# e1-tracer.net
KiCad netlist of a schematic drawn in EAGLE
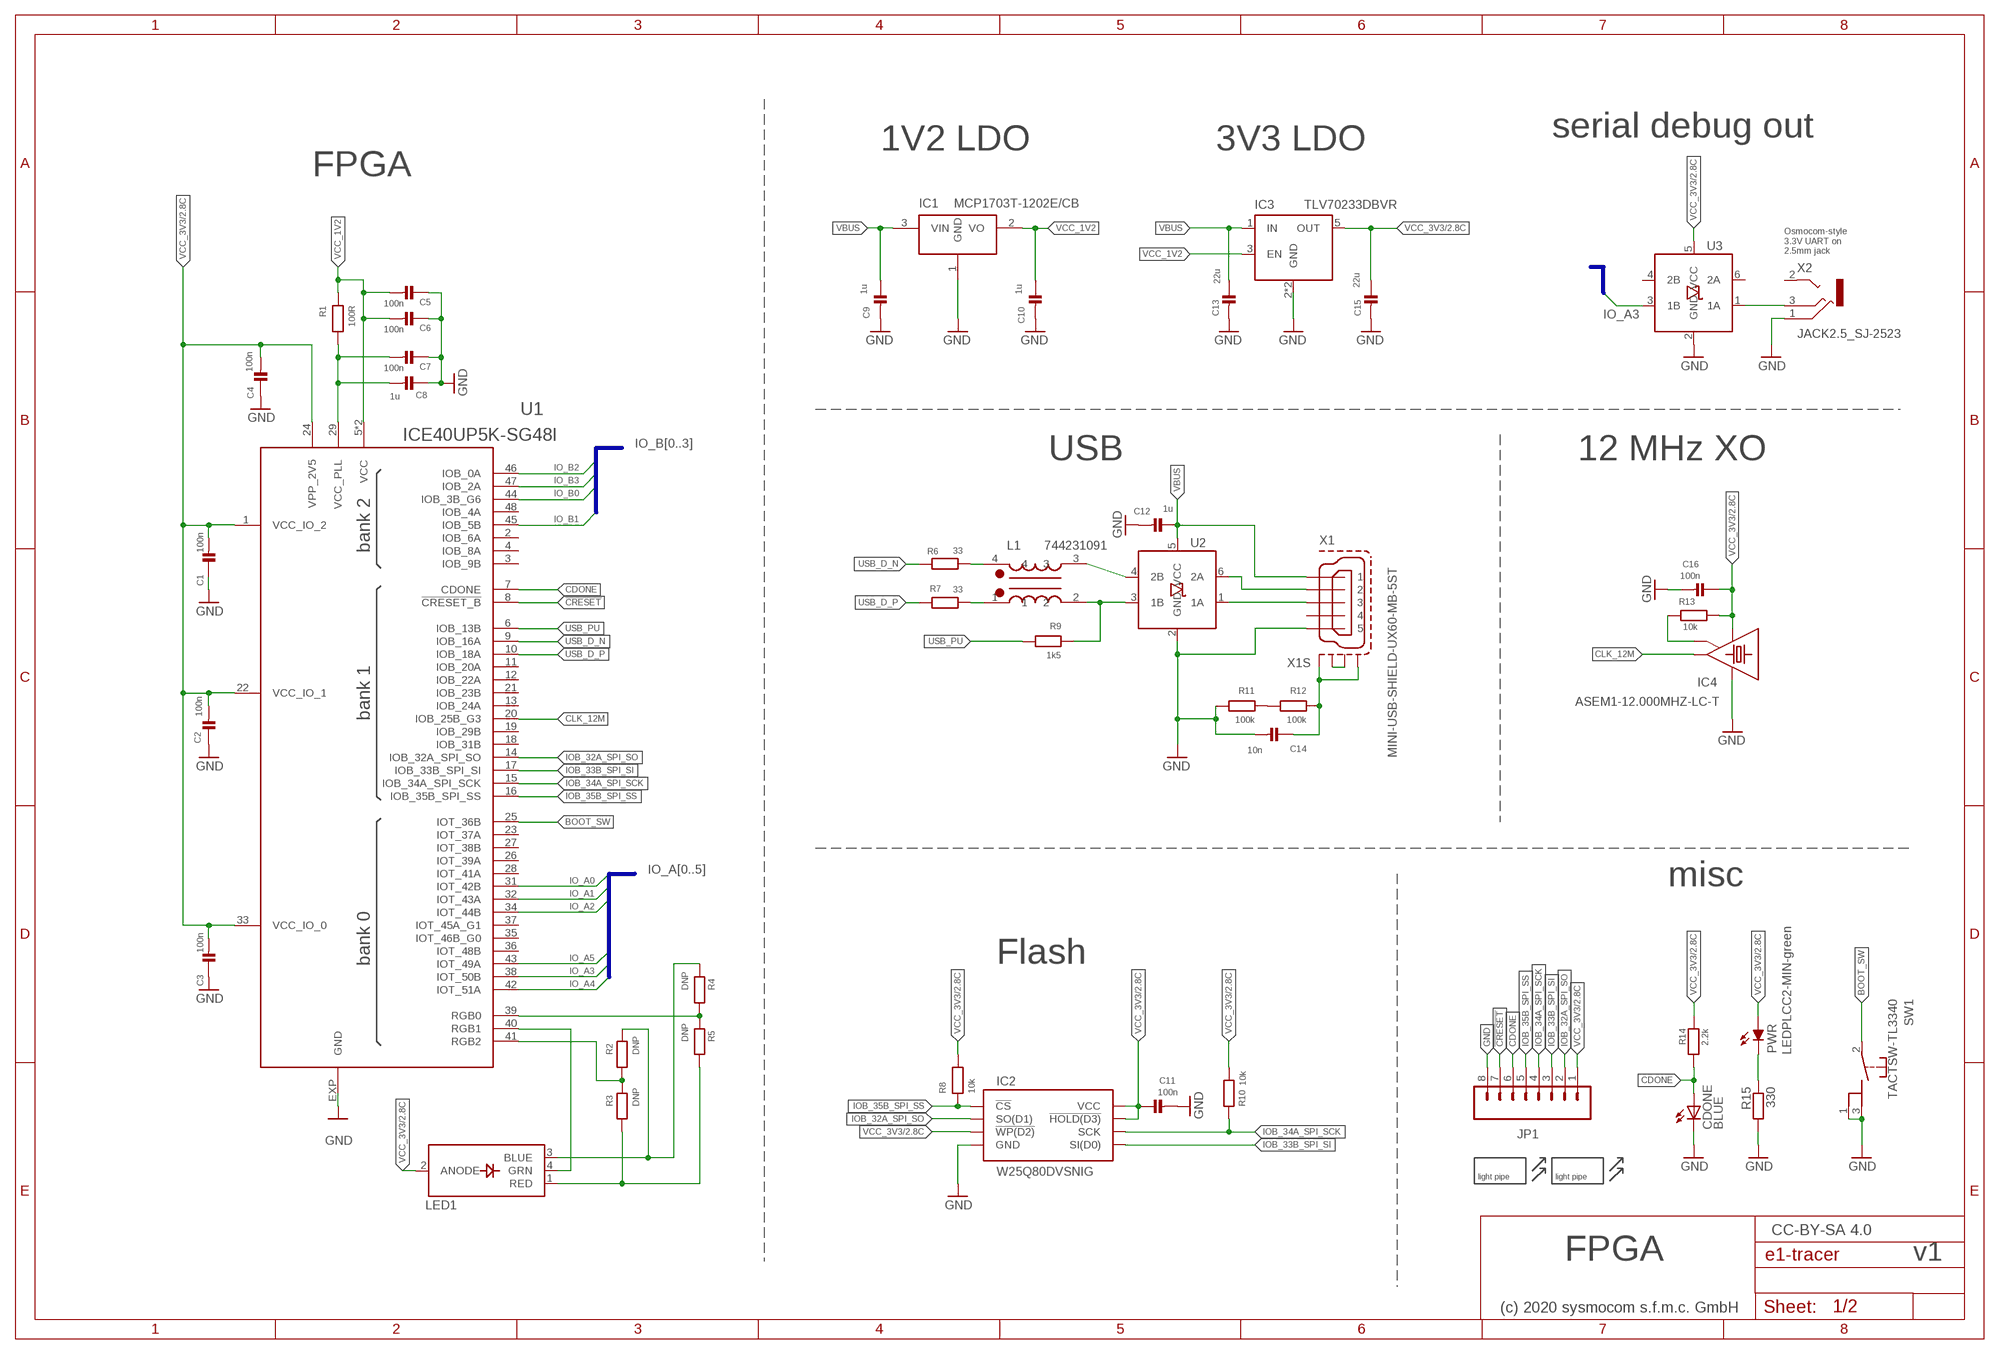
[diagram p0: schematic, sheet 1]
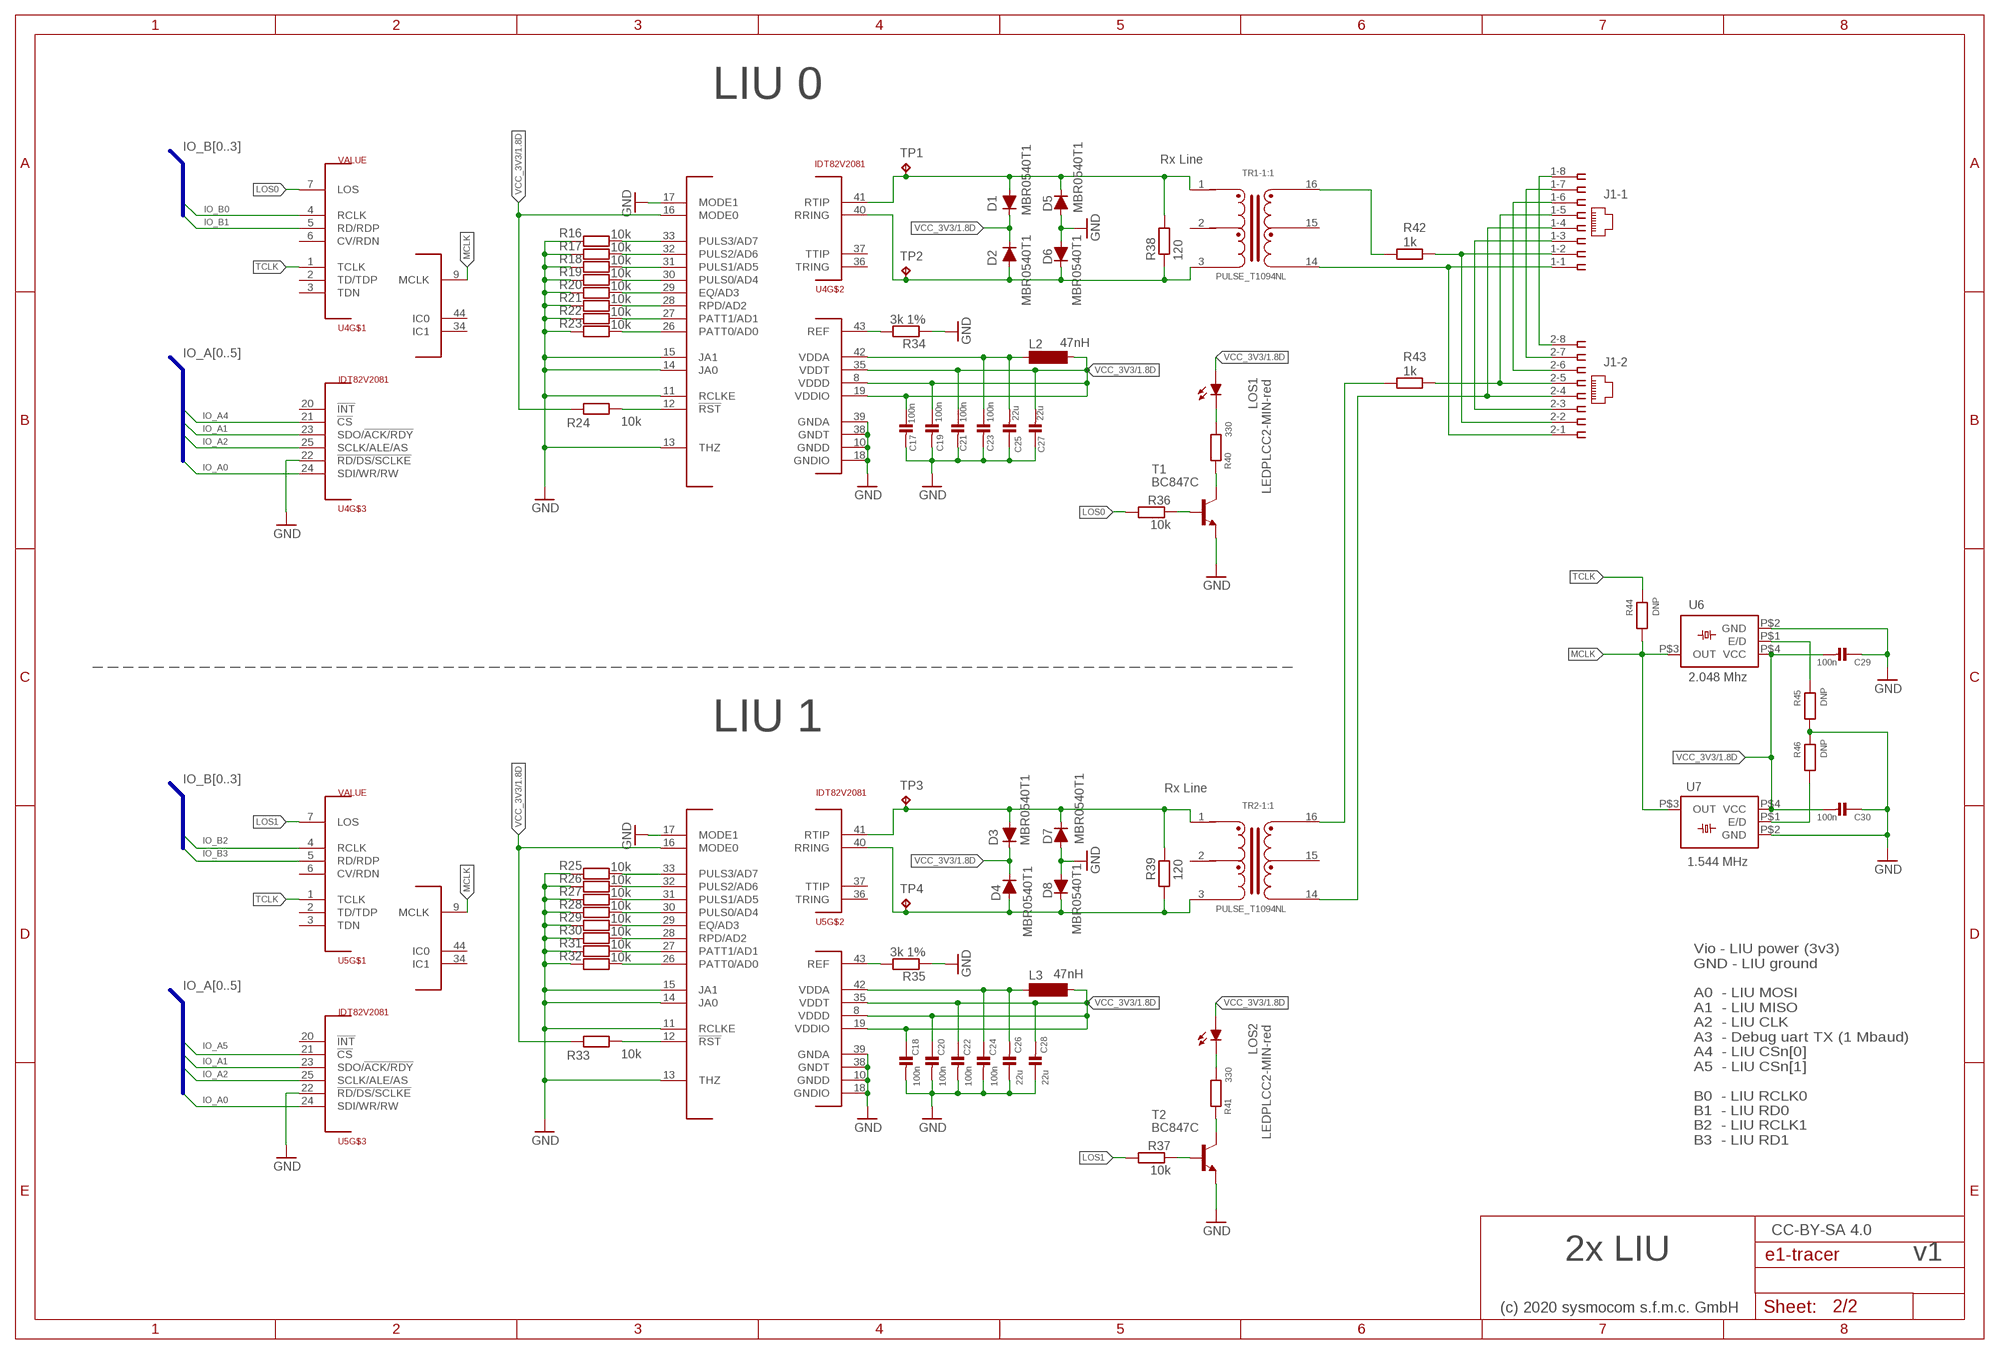
[diagram p1: schematic, sheet 2]

(export (version "E")
  (design (tool "Eeschema 10.0.6"))
  (components
    (comp (ref "C1")
      (value "100n")
      (footprint "eagle-import:_0603")
      (description "CAP CER 0.1UF 16V 10% X7R 0603")
      (fields
        (field (name "MANUFACTURER") "Samsung Electro-Mechanics America, Inc")
        (field (name "MANUFACTURERPARTNUMBER") "CL10B104KO8NNNC")
      )
      (libsource (lib "eagle-import") (part "CAP_CERAMIC_0603"))
    )
    (comp (ref "C2")
      (value "100n")
      (footprint "eagle-import:_0603")
      (description "CAP CER 0.1UF 16V 10% X7R 0603")
      (fields
        (field (name "MANUFACTURER") "Samsung Electro-Mechanics America, Inc")
        (field (name "MANUFACTURERPARTNUMBER") "CL10B104KO8NNNC")
      )
      (libsource (lib "eagle-import") (part "CAP_CERAMIC_0603"))
    )
    (comp (ref "C3")
      (value "100n")
      (footprint "eagle-import:_0603")
      (description "CAP CER 0.1UF 16V 10% X7R 0603")
      (fields
        (field (name "MANUFACTURER") "Samsung Electro-Mechanics America, Inc")
        (field (name "MANUFACTURERPARTNUMBER") "CL10B104KO8NNNC")
      )
      (libsource (lib "eagle-import") (part "CAP_CERAMIC_0603"))
    )
    (comp (ref "C4")
      (value "100n")
      (footprint "eagle-import:_0603")
      (description "CAP CER 0.1UF 16V 10% X7R 0603")
      (fields
        (field (name "MANUFACTURER") "Samsung Electro-Mechanics America, Inc")
        (field (name "MANUFACTURERPARTNUMBER") "CL10B104KO8NNNC")
      )
      (libsource (lib "eagle-import") (part "CAP_CERAMIC_0603"))
    )
    (comp (ref "C5")
      (value "100n")
      (footprint "eagle-import:_0603")
      (description "CAP CER 0.1UF 16V 10% X7R 0603")
      (fields
        (field (name "MANUFACTURER") "Samsung Electro-Mechanics America, Inc")
        (field (name "MANUFACTURERPARTNUMBER") "CL10B104KO8NNNC")
      )
      (libsource (lib "eagle-import") (part "CAP_CERAMIC_0603"))
    )
    (comp (ref "C6")
      (value "100n")
      (footprint "eagle-import:_0603")
      (description "CAP CER 0.1UF 16V 10% X7R 0603")
      (fields
        (field (name "MANUFACTURER") "Samsung Electro-Mechanics America, Inc")
        (field (name "MANUFACTURERPARTNUMBER") "CL10B104KO8NNNC")
      )
      (libsource (lib "eagle-import") (part "CAP_CERAMIC_0603"))
    )
    (comp (ref "C7")
      (value "100n")
      (footprint "eagle-import:_0603")
      (description "CAP CER 0.1UF 16V 10% X7R 0603")
      (fields
        (field (name "MANUFACTURER") "Samsung Electro-Mechanics America, Inc")
        (field (name "MANUFACTURERPARTNUMBER") "CL10B104KO8NNNC")
      )
      (libsource (lib "eagle-import") (part "CAP_CERAMIC_0603"))
    )
    (comp (ref "C8")
      (value "1u")
      (footprint "eagle-import:_0603")
      (description "CAP CER 1UF 10V X5R 0603")
      (fields
        (field (name "MANUFACTURER") "Samsung Electro-Mechanics")
        (field (name "MANUFACTURERPARTNUMBER") "CL10A105KP8NNNC")
      )
      (libsource (lib "eagle-import") (part "CAP_CERAMIC_0603"))
    )
    (comp (ref "C9")
      (value "1u")
      (footprint "eagle-import:_0603")
      (description "CAP CER 1UF 10V X5R 0603")
      (fields
        (field (name "MANUFACTURER") "Samsung Electro-Mechanics")
        (field (name "MANUFACTURERPARTNUMBER") "CL10A105KP8NNNC")
      )
      (libsource (lib "eagle-import") (part "CAP_CERAMIC_0603"))
    )
    (comp (ref "C10")
      (value "1u")
      (footprint "eagle-import:_0603")
      (description "CAP CER 1UF 10V X5R 0603")
      (fields
        (field (name "MANUFACTURER") "Samsung Electro-Mechanics")
        (field (name "MANUFACTURERPARTNUMBER") "CL10A105KP8NNNC")
      )
      (libsource (lib "eagle-import") (part "CAP_CERAMIC_0603"))
    )
    (comp (ref "C11")
      (value "100n")
      (footprint "eagle-import:_0603")
      (description "CAP CER 0.1UF 16V 10% X7R 0603")
      (fields
        (field (name "MANUFACTURER") "Samsung Electro-Mechanics America, Inc")
        (field (name "MANUFACTURERPARTNUMBER") "CL10B104KO8NNNC")
      )
      (libsource (lib "eagle-import") (part "CAP_CERAMIC_0603"))
    )
    (comp (ref "C12")
      (value "1u")
      (footprint "eagle-import:_0603")
      (description "CAP CER 1UF 10V X5R 0603")
      (fields
        (field (name "MANUFACTURER") "Samsung Electro-Mechanics")
        (field (name "MANUFACTURERPARTNUMBER") "CL10A105KP8NNNC")
      )
      (libsource (lib "eagle-import") (part "CAP_CERAMIC_0603"))
    )
    (comp (ref "C13")
      (value "22u")
      (footprint "eagle-import:1206")
      (description "CAP CER 22UF 10V 10% X5R 1206")
      (fields
        (field (name "MANUFACTURER") "Samsung Electro-Mechanics America, Inc")
        (field (name "MANUFACTURERPARTNUMBER") "CL31A226KPHNNNE")
      )
      (libsource (lib "eagle-import") (part "CAP_CERAMIC1206"))
    )
    (comp (ref "C14")
      (value "10n")
      (footprint "eagle-import:_0402")
      (description "CAP CER 10000PF 25V X7R 0402")
      (fields
        (field (name "MANUFACTURER") "Samsung Electro-Mechanics")
        (field (name "MANUFACTURERPARTNUMBER") "CL05B103KA5NNNC")
      )
      (libsource (lib "eagle-import") (part "CAP_CERAMIC_0402"))
    )
    (comp (ref "C15")
      (value "22u")
      (footprint "eagle-import:1206")
      (description "CAP CER 22UF 10V 10% X5R 1206")
      (fields
        (field (name "MANUFACTURER") "Samsung Electro-Mechanics America, Inc")
        (field (name "MANUFACTURERPARTNUMBER") "CL31A226KPHNNNE")
      )
      (libsource (lib "eagle-import") (part "CAP_CERAMIC1206"))
    )
    (comp (ref "C16")
      (value "100n")
      (footprint "eagle-import:_0603")
      (description "CAP CER 0.1UF 16V 10% X7R 0603")
      (fields
        (field (name "MANUFACTURER") "Samsung Electro-Mechanics America, Inc")
        (field (name "MANUFACTURERPARTNUMBER") "CL10B104KO8NNNC")
      )
      (libsource (lib "eagle-import") (part "CAP_CERAMIC_0603"))
    )
    (comp (ref "CDONE")
      (value "BLUE")
      (footprint "eagle-import:CHIPLED_0603")
      (description "LED BLUE CLEAR CHIP SMD")
      (fields
        (field (name "MANUFACTURER") "Lite-On Inc.")
        (field (name "MANUFACTURERPARTNUMBER") "LTST-C193TBKT-5A")
      )
      (libsource (lib "eagle-import") (part "LEDCHIPLED_0603"))
    )
    (comp (ref "IC1")
      (value "MCP1703T-1202E/CB")
      (footprint "eagle-import:SOT23-3")
      (description "IC REG LIN 1.2V 200MA SOT23A-3")
      (fields (field (name "MANUFACTURER") "Microchip Technology"))
      (libsource (lib "eagle-import") (part "MCP1700"))
    )
    (comp (ref "IC2")
      (value "W25Q80DVSNIG")
      (footprint "eagle-import:SO08COMBINED")
      (description "IC FLASH 8M SPI 104MHZ 8SOIC")
      (fields (field (name "MANUFACTURER") "Winbond Electronics"))
      (libsource (lib "eagle-import") (part "AT25SF-COMB"))
    )
    (comp (ref "IC3")
      (value "TLV70233DBVR")
      (footprint "eagle-import:SOT23-DBV")
      (description "IC REG LINEAR 3.3V 300MA SOT23-5")
      (fields (field (name "MANUFACTURER") "Texas Instruments") (field (name "OC_DIGIKEY") "296-32415-1-ND"))
      (libsource (lib "eagle-import") (part "TLV700-SOT33"))
    )
    (comp (ref "IC4")
      (value "ASEM1-12.000MHZ-LC-T")
      (footprint "eagle-import:TSX-3225")
      (description "MEMS OSC XO 12.0000MHZ CMOS SMD")
      (fields (field (name "MANUFACTURER") "Abracon LLC"))
      (libsource (lib "eagle-import") (part "ASTMLP-E-OSC"))
    )
    (comp (ref "JP1")
      (value "M08LOCK")
      (footprint "eagle-import:1X08_LOCK")
      (description "NO DESCRIPTION")
      (fields
        (field (name "MANUFACTURER") "UNKNOWN MANUFACTURER")
        (field (name "MANUFACTURERPARTNUMBER") "UNKNOWN MANUFACTURER PART NUMBER")
      )
      (libsource (lib "eagle-import") (part "M08LOCK"))
    )
    (comp (ref "L1")
      (value "744231091")
      (footprint "eagle-import:WE-CNSW_0805")
      (description "CMC 370MA 2LN 90 OHM SMD")
      (fields (field (name "MANUFACTURER") "Wurth Electronics Inc."))
      (libsource (lib "eagle-import") (part "WE-CNSW_0805"))
    )
    (comp (ref "LED1")
      (value "LED_RGB_PLCC4")
      (footprint "eagle-import:RGBLED_PLCC4")
      (description "LED RGB DIFFUSED 4PLCC SMD")
      (fields
        (field (name "MANUFACTURER") "TT Electronics/Optek Technology")
        (field (name "MANUFACTURERPARTNUMBER") "OVSARGB4R8")
      )
      (libsource (lib "eagle-import") (part "LED_RGB_PLCC4"))
    )
    (comp (ref "M1")
      (value "MENTOR_12701001")
      (footprint "eagle-import:1270.1001")
      (description "NO DESCRIPTION")
      (fields (field (name "MANUFACTURER") "Mentor") (field (name "MANUFACTURERPARTNUMBER") "1270.1001"))
      (libsource (lib "eagle-import") (part "MENTOR_12701001"))
    )
    (comp (ref "M2")
      (value "MENTOR_12701001")
      (footprint "eagle-import:1270.1001")
      (description "NO DESCRIPTION")
      (fields (field (name "MANUFACTURER") "Mentor") (field (name "MANUFACTURERPARTNUMBER") "1270.1001"))
      (libsource (lib "eagle-import") (part "MENTOR_12701001"))
    )
    (comp (ref "PWR")
      (value "LEDPLCC2-MIN-green")
      (footprint "eagle-import:PLCC2-MIN")
      (description "LED GREEN CLEAR 2PLCC SMD")
      (fields
        (field (name "MANUFACTURER") "Rohm Semiconductor")
        (field (name "MANUFACTURERPARTNUMBER") "SML-Z14PTT86A")
      )
      (libsource (lib "eagle-import") (part "LEDPLCC2-MIN"))
    )
    (comp (ref "R1")
      (value "100R")
      (footprint "eagle-import:_0603")
      (description "RES 100 OHM 5%% 1/10W 0603")
      (fields
        (field (name "MANUFACTURER") "Stackpole Electronics Inc")
        (field (name "MANUFACTURERPARTNUMBER") "RMCF0603JT100R")
      )
      (libsource (lib "eagle-import") (part "RESISTOR_0603"))
    )
    (comp (ref "R2")
      (value "DNP")
      (footprint "eagle-import:_0603")
      (description "RES SMD 0 OHM JUMPER 1/10W 0603")
      (fields
        (field (name "MANUFACTURER") "Panasonic Electronic Components")
        (field (name "MANUFACTURERPARTNUMBER") "ERJ-3GEY0R00V")
      )
      (libsource (lib "eagle-import") (part "RESISTOR_0603"))
    )
    (comp (ref "R3")
      (value "DNP")
      (footprint "eagle-import:_0603")
      (description "RES SMD 0 OHM JUMPER 1/10W 0603")
      (fields
        (field (name "MANUFACTURER") "Panasonic Electronic Components")
        (field (name "MANUFACTURERPARTNUMBER") "ERJ-3GEY0R00V")
      )
      (libsource (lib "eagle-import") (part "RESISTOR_0603"))
    )
    (comp (ref "R4")
      (value "DNP")
      (footprint "eagle-import:_0603")
      (description "RES SMD 0 OHM JUMPER 1/10W 0603")
      (fields
        (field (name "MANUFACTURER") "Panasonic Electronic Components")
        (field (name "MANUFACTURERPARTNUMBER") "ERJ-3GEY0R00V")
      )
      (libsource (lib "eagle-import") (part "RESISTOR_0603"))
    )
    (comp (ref "R5")
      (value "DNP")
      (footprint "eagle-import:_0603")
      (description "RES SMD 0 OHM JUMPER 1/10W 0603")
      (fields
        (field (name "MANUFACTURER") "Panasonic Electronic Components")
        (field (name "MANUFACTURERPARTNUMBER") "ERJ-3GEY0R00V")
      )
      (libsource (lib "eagle-import") (part "RESISTOR_0603"))
    )
    (comp (ref "R6")
      (value "33")
      (footprint "eagle-import:_0402")
      (description "RES 33 OHM 5%% 1/10W 0603")
      (fields
        (field (name "MANUFACTURER") "Stackpole Electronics Inc")
        (field (name "MANUFACTURERPARTNUMBER") "RMCF0603JT33R0")
      )
      (libsource (lib "eagle-import") (part "RESISTOR_0402"))
    )
    (comp (ref "R7")
      (value "33")
      (footprint "eagle-import:_0402")
      (description "RES 33 OHM 5%% 1/10W 0603")
      (fields
        (field (name "MANUFACTURER") "Stackpole Electronics Inc")
        (field (name "MANUFACTURERPARTNUMBER") "RMCF0603JT33R0")
      )
      (libsource (lib "eagle-import") (part "RESISTOR_0402"))
    )
    (comp (ref "R8")
      (value "10k")
      (footprint "eagle-import:_0603")
      (description "RES 10K OHM 5%% 1/10W 0603")
      (fields
        (field (name "MANUFACTURER") "Stackpole Electronics Inc")
        (field (name "MANUFACTURERPARTNUMBER") "RMCF0603JT10K0")
      )
      (libsource (lib "eagle-import") (part "RESISTOR_0603"))
    )
    (comp (ref "R9")
      (value "1k5")
      (footprint "eagle-import:_0603")
      (description "RES 1.5K OHM 5%% 1/10W 0603")
      (fields
        (field (name "MANUFACTURER") "Stackpole Electronics Inc")
        (field (name "MANUFACTURERPARTNUMBER") "RMCF0603JT1K50")
      )
      (libsource (lib "eagle-import") (part "RESISTOR_0603"))
    )
    (comp (ref "R10")
      (value "10k")
      (footprint "eagle-import:_0603")
      (description "RES 10K OHM 5%% 1/10W 0603")
      (fields
        (field (name "MANUFACTURER") "Stackpole Electronics Inc")
        (field (name "MANUFACTURERPARTNUMBER") "RMCF0603JT10K0")
      )
      (libsource (lib "eagle-import") (part "RESISTOR_0603"))
    )
    (comp (ref "R11")
      (value "100k")
      (footprint "eagle-import:_0603")
      (description "RES SMD 100K OHM 5%% 1/10W 0603")
      (fields
        (field (name "MANUFACTURER") "Yageo")
        (field (name "MANUFACTURERPARTNUMBER") "RC0603JR-07100KL")
      )
      (libsource (lib "eagle-import") (part "RESISTOR_0603"))
    )
    (comp (ref "R12")
      (value "100k")
      (footprint "eagle-import:_0603")
      (description "RES SMD 100K OHM 5%% 1/10W 0603")
      (fields
        (field (name "MANUFACTURER") "Yageo")
        (field (name "MANUFACTURERPARTNUMBER") "RC0603JR-07100KL")
      )
      (libsource (lib "eagle-import") (part "RESISTOR_0603"))
    )
    (comp (ref "R13")
      (value "10k")
      (footprint "eagle-import:_0603")
      (description "RES 10K OHM 5%% 1/10W 0603")
      (fields
        (field (name "MANUFACTURER") "Stackpole Electronics Inc")
        (field (name "MANUFACTURERPARTNUMBER") "RMCF0603JT10K0")
      )
      (libsource (lib "eagle-import") (part "RESISTOR_0603"))
    )
    (comp (ref "R14")
      (value "2.2k")
      (footprint "eagle-import:_0603")
      (description "RES 2.2K OHM 5%% 1/10W 0603")
      (fields
        (field (name "MANUFACTURER") "Stackpole Electronics Inc")
        (field (name "MANUFACTURERPARTNUMBER") "RMCF0603JT2K20")
      )
      (libsource (lib "eagle-import") (part "RESISTOR_0603"))
    )
    (comp (ref "R15")
      (value "330")
      (footprint "eagle-import:_0603")
      (description "RES SMD 330 OHM 1%% 1/10W 0603")
      (fields
        (field (name "MANUFACTURER") "Yageo")
        (field (name "MANUFACTURERPARTNUMBER") "RC0603FR-07330RL")
      )
      (libsource (lib "eagle-import") (part "RESISTOR_0603"))
    )
    (comp (ref "SW1")
      (value "TACTSW-TL3340")
      (footprint "eagle-import:TL3340-ORIG")
      (description "SWITCH TACTILE SPST-NO 0.05A 12V")
      (fields
        (field (name "MANUFACTURER") "E-Switch")
        (field (name "MANUFACTURERPARTNUMBER") "TL3340AF160QG")
      )
      (libsource (lib "eagle-import") (part "TL3340"))
    )
    (comp (ref "U1")
      (value "ICE40UP5K-SG48I")
      (footprint "eagle-import:QFN48")
      (description "IC FPGA 39 I/O 48QFN")
      (fields (field (name "MANUFACTURER") "Lattice Semiconductor Corporation"))
      (libsource (lib "eagle-import") (part "ICE40UP5K-SG48I"))
    )
    (comp (ref "U2")
      (value "IP4234CZ6")
      (footprint "eagle-import:TSOP-6")
      (description "TVS DIODE 5.5V 6TSOP")
      (fields
        (field (name "MANUFACTURER") "Nexperia USA Inc.")
        (field (name "MANUFACTURERPARTNUMBER") "IP4234CZ6,125")
      )
      (libsource (lib "eagle-import") (part "IP4234CZ6"))
    )
    (comp (ref "U3")
      (value "IP4234CZ6")
      (footprint "eagle-import:TSOP-6")
      (description "TVS DIODE 5.5V 6TSOP")
      (fields
        (field (name "MANUFACTURER") "Nexperia USA Inc.")
        (field (name "MANUFACTURERPARTNUMBER") "IP4234CZ6,125")
      )
      (libsource (lib "eagle-import") (part "IP4234CZ6"))
    )
    (comp (ref "X1")
      (value "MINI-USB-SHIELD-UX60-MB-5ST")
      (footprint "eagle-import:UX60-MB-5ST")
      (description "CONN RCPT USB2.0 MINI B SMD R/A")
      (fields
        (field (name "MANUFACTURER") "Hirose Electric Co Ltd")
        (field (name "MANUFACTURERPARTNUMBER") "UX60A-MB-5ST")
        (field (name "CLASS") "CONNECTOR")
        (field (name "LINK") "https://www.digikey.de/product-detail/de/hirose-electric-co-ltd/UX60A-MB-5ST/H2961CT-ND/597540")
        (field (name "POPULATED") "TRUE")
        (field (name "ROHSCERTIFICATE") "Bleifrei / RoHS-konform")
        (field (name "SOURCE") "DIGIKEY")
        (field (name "SOURCEPARTNUMBER") "H2961CT-ND")
      )
      (libsource (lib "eagle-import") (part "MINI-USB-SHIELD-UX60-MB-5ST"))
    )
    (comp (ref "X2")
      (value "JACK2.5_SJ-2523")
      (footprint "eagle-import:JACK2.5_SJ-2523")
      (description "CONN JACK STEREO 2.5MM SMD R/A")
      (fields
        (field (name "MANUFACTURER") "CUI Inc.")
        (field (name "MANUFACTURERPARTNUMBER") "SJ-2523-SMT-TR")
      )
      (libsource (lib "eagle-import") (part "JACK2.5_SJ-2523"))
    )
    (comp (ref "C17")
      (value "100n")
      (footprint "eagle-import:_0603")
      (description "CAP CER 0.1UF 16V 10% X7R 0603")
      (fields
        (field (name "MANUFACTURER") "Samsung Electro-Mechanics America, Inc")
        (field (name "MANUFACTURERPARTNUMBER") "CL10B104KO8NNNC")
      )
      (libsource (lib "eagle-import") (part "CAP_CERAMIC_0603"))
    )
    (comp (ref "C18")
      (value "100n")
      (footprint "eagle-import:_0603")
      (description "CAP CER 0.1UF 16V 10% X7R 0603")
      (fields
        (field (name "MANUFACTURER") "Samsung Electro-Mechanics America, Inc")
        (field (name "MANUFACTURERPARTNUMBER") "CL10B104KO8NNNC")
      )
      (libsource (lib "eagle-import") (part "CAP_CERAMIC_0603"))
    )
    (comp (ref "C19")
      (value "100n")
      (footprint "eagle-import:_0603")
      (description "CAP CER 0.1UF 16V 10% X7R 0603")
      (fields
        (field (name "MANUFACTURER") "Samsung Electro-Mechanics America, Inc")
        (field (name "MANUFACTURERPARTNUMBER") "CL10B104KO8NNNC")
      )
      (libsource (lib "eagle-import") (part "CAP_CERAMIC_0603"))
    )
    (comp (ref "C20")
      (value "100n")
      (footprint "eagle-import:_0603")
      (description "CAP CER 0.1UF 16V 10% X7R 0603")
      (fields
        (field (name "MANUFACTURER") "Samsung Electro-Mechanics America, Inc")
        (field (name "MANUFACTURERPARTNUMBER") "CL10B104KO8NNNC")
      )
      (libsource (lib "eagle-import") (part "CAP_CERAMIC_0603"))
    )
    (comp (ref "C21")
      (value "100n")
      (footprint "eagle-import:_0603")
      (description "CAP CER 0.1UF 16V 10% X7R 0603")
      (fields
        (field (name "MANUFACTURER") "Samsung Electro-Mechanics America, Inc")
        (field (name "MANUFACTURERPARTNUMBER") "CL10B104KO8NNNC")
      )
      (libsource (lib "eagle-import") (part "CAP_CERAMIC_0603"))
    )
    (comp (ref "C22")
      (value "100n")
      (footprint "eagle-import:_0603")
      (description "CAP CER 0.1UF 16V 10% X7R 0603")
      (fields
        (field (name "MANUFACTURER") "Samsung Electro-Mechanics America, Inc")
        (field (name "MANUFACTURERPARTNUMBER") "CL10B104KO8NNNC")
      )
      (libsource (lib "eagle-import") (part "CAP_CERAMIC_0603"))
    )
    (comp (ref "C23")
      (value "100n")
      (footprint "eagle-import:_0603")
      (description "CAP CER 0.1UF 16V 10% X7R 0603")
      (fields
        (field (name "MANUFACTURER") "Samsung Electro-Mechanics America, Inc")
        (field (name "MANUFACTURERPARTNUMBER") "CL10B104KO8NNNC")
      )
      (libsource (lib "eagle-import") (part "CAP_CERAMIC_0603"))
    )
    (comp (ref "C24")
      (value "100n")
      (footprint "eagle-import:_0603")
      (description "CAP CER 0.1UF 16V 10% X7R 0603")
      (fields
        (field (name "MANUFACTURER") "Samsung Electro-Mechanics America, Inc")
        (field (name "MANUFACTURERPARTNUMBER") "CL10B104KO8NNNC")
      )
      (libsource (lib "eagle-import") (part "CAP_CERAMIC_0603"))
    )
    (comp (ref "C25")
      (value "22u")
      (footprint "eagle-import:_0805")
      (description "CAP CER 22UF 6.3V X5R 0805")
      (fields
        (field (name "MANUFACTURER") "KEMET")
        (field (name "MANUFACTURERPARTNUMBER") "C0805C226M9PACTU")
      )
      (libsource (lib "eagle-import") (part "CAP_CERAMIC_0805"))
    )
    (comp (ref "C26")
      (value "22u")
      (footprint "eagle-import:_0805")
      (description "CAP CER 22UF 6.3V X5R 0805")
      (fields
        (field (name "MANUFACTURER") "KEMET")
        (field (name "MANUFACTURERPARTNUMBER") "C0805C226M9PACTU")
      )
      (libsource (lib "eagle-import") (part "CAP_CERAMIC_0805"))
    )
    (comp (ref "C27")
      (value "22u")
      (footprint "eagle-import:_0805")
      (description "CAP CER 22UF 6.3V X5R 0805")
      (fields
        (field (name "MANUFACTURER") "KEMET")
        (field (name "MANUFACTURERPARTNUMBER") "C0805C226M9PACTU")
      )
      (libsource (lib "eagle-import") (part "CAP_CERAMIC_0805"))
    )
    (comp (ref "C28")
      (value "22u")
      (footprint "eagle-import:_0805")
      (description "CAP CER 22UF 6.3V X5R 0805")
      (fields
        (field (name "MANUFACTURER") "KEMET")
        (field (name "MANUFACTURERPARTNUMBER") "C0805C226M9PACTU")
      )
      (libsource (lib "eagle-import") (part "CAP_CERAMIC_0805"))
    )
    (comp (ref "C29")
      (value "100n")
      (footprint "eagle-import:_0603")
      (description "CAP CER 0.1UF 16V 10% X7R 0603")
      (fields
        (field (name "MANUFACTURER") "Samsung Electro-Mechanics America, Inc")
        (field (name "MANUFACTURERPARTNUMBER") "CL10B104KO8NNNC")
      )
      (libsource (lib "eagle-import") (part "CAP_CERAMIC_0603"))
    )
    (comp (ref "C30")
      (value "100n")
      (footprint "eagle-import:_0603")
      (description "CAP CER 0.1UF 16V 10% X7R 0603")
      (fields
        (field (name "MANUFACTURER") "Samsung Electro-Mechanics America, Inc")
        (field (name "MANUFACTURERPARTNUMBER") "CL10B104KO8NNNC")
      )
      (libsource (lib "eagle-import") (part "CAP_CERAMIC_0603"))
    )
    (comp (ref "D1")
      (value "MBR0540T1")
      (footprint "eagle-import:SOD123")
      (description "DIODE SCHOTTKY 40V 500MA SOD123")
      (fields
        (field (name "MANUFACTURER") "ON Semiconductor")
        (field (name "MANUFACTURERPARTNUMBER") "MBR0540T1G")
      )
      (libsource (lib "eagle-import") (part "D-FILL-SOD123"))
    )
    (comp (ref "D2")
      (value "MBR0540T1")
      (footprint "eagle-import:SOD123")
      (description "DIODE SCHOTTKY 40V 500MA SOD123")
      (fields
        (field (name "MANUFACTURER") "ON Semiconductor")
        (field (name "MANUFACTURERPARTNUMBER") "MBR0540T1G")
      )
      (libsource (lib "eagle-import") (part "D-FILL-SOD123"))
    )
    (comp (ref "D3")
      (value "MBR0540T1")
      (footprint "eagle-import:SOD123")
      (description "DIODE SCHOTTKY 40V 500MA SOD123")
      (fields
        (field (name "MANUFACTURER") "ON Semiconductor")
        (field (name "MANUFACTURERPARTNUMBER") "MBR0540T1G")
      )
      (libsource (lib "eagle-import") (part "D-FILL-SOD123"))
    )
    (comp (ref "D4")
      (value "MBR0540T1")
      (footprint "eagle-import:SOD123")
      (description "DIODE SCHOTTKY 40V 500MA SOD123")
      (fields
        (field (name "MANUFACTURER") "ON Semiconductor")
        (field (name "MANUFACTURERPARTNUMBER") "MBR0540T1G")
      )
      (libsource (lib "eagle-import") (part "D-FILL-SOD123"))
    )
    (comp (ref "D5")
      (value "MBR0540T1")
      (footprint "eagle-import:SOD123")
      (description "DIODE SCHOTTKY 40V 500MA SOD123")
      (fields
        (field (name "MANUFACTURER") "ON Semiconductor")
        (field (name "MANUFACTURERPARTNUMBER") "MBR0540T1G")
      )
      (libsource (lib "eagle-import") (part "D-FILL-SOD123"))
    )
    (comp (ref "D6")
      (value "MBR0540T1")
      (footprint "eagle-import:SOD123")
      (description "DIODE SCHOTTKY 40V 500MA SOD123")
      (fields
        (field (name "MANUFACTURER") "ON Semiconductor")
        (field (name "MANUFACTURERPARTNUMBER") "MBR0540T1G")
      )
      (libsource (lib "eagle-import") (part "D-FILL-SOD123"))
    )
    (comp (ref "D7")
      (value "MBR0540T1")
      (footprint "eagle-import:SOD123")
      (description "DIODE SCHOTTKY 40V 500MA SOD123")
      (fields
        (field (name "MANUFACTURER") "ON Semiconductor")
        (field (name "MANUFACTURERPARTNUMBER") "MBR0540T1G")
      )
      (libsource (lib "eagle-import") (part "D-FILL-SOD123"))
    )
    (comp (ref "D8")
      (value "MBR0540T1")
      (footprint "eagle-import:SOD123")
      (description "DIODE SCHOTTKY 40V 500MA SOD123")
      (fields
        (field (name "MANUFACTURER") "ON Semiconductor")
        (field (name "MANUFACTURERPARTNUMBER") "MBR0540T1G")
      )
      (libsource (lib "eagle-import") (part "D-FILL-SOD123"))
    )
    (comp (ref "J1")
      (value "PASSTHROUGH")
      (footprint "eagle-import:557560-1")
      (description "CONN MOD JACK 8P8C R/A UNSHLD")
      (fields
        (field (name "MANUFACTURER") "TE Connectivity AMP Connectors")
        (field (name "MANUFACTURERPARTNUMBER") "5557560-1")
        (field (name "CLASS") "CONNECTOR\\JUMPER")
        (field (name "LINK") "https://www.digikey.de/product-detail/de/te-connectivity-amp-connectors/5557560-1/A31449-ND")
        (field (name "POPULATED") "TRUE")
        (field (name "ROHSCERTIFICATE") "UNKNOWN ROHS CERTIFICATE")
        (field (name "SOURCE") "DIGIKEY")
        (field (name "SOURCEPARTNUMBER") "A31449-ND")
      )
      (libsource (lib "eagle-import") (part "557560-1"))
    )
    (comp (ref "L2")
      (value "47nH")
      (footprint "eagle-import:SM-1206")
      (description "FIXED IND 47NH 300MA 700MOHM SMD")
      (fields
        (field (name "MANUFACTURER") "Bourns Inc.")
        (field (name "MANUFACTURERPARTNUMBER") "CE201210-47NJ")
      )
      (libsource (lib "eagle-import") (part "SM-1206"))
    )
    (comp (ref "L3")
      (value "47nH")
      (footprint "eagle-import:SM-1206")
      (description "FIXED IND 47NH 300MA 700MOHM SMD")
      (fields
        (field (name "MANUFACTURER") "Bourns Inc.")
        (field (name "MANUFACTURERPARTNUMBER") "CE201210-47NJ")
      )
      (libsource (lib "eagle-import") (part "SM-1206"))
    )
    (comp (ref "LOS1")
      (value "LEDPLCC2-MIN-red")
      (footprint "eagle-import:PLCC2-MIN")
      (description "LED RED CLEAR 2PLCC SMD")
      (fields
        (field (name "MANUFACTURER") "OSRAM Opto Semiconductors Inc.")
        (field (name "MANUFACTURERPARTNUMBER") "LS T676-R1S1-1-Z")
      )
      (libsource (lib "eagle-import") (part "LEDPLCC2-MIN"))
    )
    (comp (ref "LOS2")
      (value "LEDPLCC2-MIN-red")
      (footprint "eagle-import:PLCC2-MIN")
      (description "LED RED CLEAR 2PLCC SMD")
      (fields
        (field (name "MANUFACTURER") "OSRAM Opto Semiconductors Inc.")
        (field (name "MANUFACTURERPARTNUMBER") "LS T676-R1S1-1-Z")
      )
      (libsource (lib "eagle-import") (part "LEDPLCC2-MIN"))
    )
    (comp (ref "R16")
      (value "10k")
      (footprint "eagle-import:_0603")
      (description "RES 10K OHM 5%% 1/10W 0603")
      (fields
        (field (name "MANUFACTURER") "Stackpole Electronics Inc")
        (field (name "MANUFACTURERPARTNUMBER") "RMCF0603JT10K0")
      )
      (libsource (lib "eagle-import") (part "RESISTOR_0603"))
    )
    (comp (ref "R17")
      (value "10k")
      (footprint "eagle-import:_0603")
      (description "RES 10K OHM 5%% 1/10W 0603")
      (fields
        (field (name "MANUFACTURER") "Stackpole Electronics Inc")
        (field (name "MANUFACTURERPARTNUMBER") "RMCF0603JT10K0")
      )
      (libsource (lib "eagle-import") (part "RESISTOR_0603"))
    )
    (comp (ref "R18")
      (value "10k")
      (footprint "eagle-import:_0603")
      (description "RES 10K OHM 5%% 1/10W 0603")
      (fields
        (field (name "MANUFACTURER") "Stackpole Electronics Inc")
        (field (name "MANUFACTURERPARTNUMBER") "RMCF0603JT10K0")
      )
      (libsource (lib "eagle-import") (part "RESISTOR_0603"))
    )
    (comp (ref "R19")
      (value "10k")
      (footprint "eagle-import:_0603")
      (description "RES 10K OHM 5%% 1/10W 0603")
      (fields
        (field (name "MANUFACTURER") "Stackpole Electronics Inc")
        (field (name "MANUFACTURERPARTNUMBER") "RMCF0603JT10K0")
      )
      (libsource (lib "eagle-import") (part "RESISTOR_0603"))
    )
    (comp (ref "R20")
      (value "10k")
      (footprint "eagle-import:_0603")
      (description "RES 10K OHM 5%% 1/10W 0603")
      (fields
        (field (name "MANUFACTURER") "Stackpole Electronics Inc")
        (field (name "MANUFACTURERPARTNUMBER") "RMCF0603JT10K0")
      )
      (libsource (lib "eagle-import") (part "RESISTOR_0603"))
    )
    (comp (ref "R21")
      (value "10k")
      (footprint "eagle-import:_0603")
      (description "RES 10K OHM 5%% 1/10W 0603")
      (fields
        (field (name "MANUFACTURER") "Stackpole Electronics Inc")
        (field (name "MANUFACTURERPARTNUMBER") "RMCF0603JT10K0")
      )
      (libsource (lib "eagle-import") (part "RESISTOR_0603"))
    )
    (comp (ref "R22")
      (value "10k")
      (footprint "eagle-import:_0603")
      (description "RES 10K OHM 5%% 1/10W 0603")
      (fields
        (field (name "MANUFACTURER") "Stackpole Electronics Inc")
        (field (name "MANUFACTURERPARTNUMBER") "RMCF0603JT10K0")
      )
      (libsource (lib "eagle-import") (part "RESISTOR_0603"))
    )
    (comp (ref "R23")
      (value "10k")
      (footprint "eagle-import:_0603")
      (description "RES 10K OHM 5%% 1/10W 0603")
      (fields
        (field (name "MANUFACTURER") "Stackpole Electronics Inc")
        (field (name "MANUFACTURERPARTNUMBER") "RMCF0603JT10K0")
      )
      (libsource (lib "eagle-import") (part "RESISTOR_0603"))
    )
    (comp (ref "R24")
      (value "10k")
      (footprint "eagle-import:_0603")
      (description "RES 10K OHM 5%% 1/10W 0603")
      (fields
        (field (name "MANUFACTURER") "Stackpole Electronics Inc")
        (field (name "MANUFACTURERPARTNUMBER") "RMCF0603JT10K0")
      )
      (libsource (lib "eagle-import") (part "RESISTOR_0603"))
    )
    (comp (ref "R25")
      (value "10k")
      (footprint "eagle-import:_0603")
      (description "RES 10K OHM 5%% 1/10W 0603")
      (fields
        (field (name "MANUFACTURER") "Stackpole Electronics Inc")
        (field (name "MANUFACTURERPARTNUMBER") "RMCF0603JT10K0")
      )
      (libsource (lib "eagle-import") (part "RESISTOR_0603"))
    )
    (comp (ref "R26")
      (value "10k")
      (footprint "eagle-import:_0603")
      (description "RES 10K OHM 5%% 1/10W 0603")
      (fields
        (field (name "MANUFACTURER") "Stackpole Electronics Inc")
        (field (name "MANUFACTURERPARTNUMBER") "RMCF0603JT10K0")
      )
      (libsource (lib "eagle-import") (part "RESISTOR_0603"))
    )
    (comp (ref "R27")
      (value "10k")
      (footprint "eagle-import:_0603")
      (description "RES 10K OHM 5%% 1/10W 0603")
      (fields
        (field (name "MANUFACTURER") "Stackpole Electronics Inc")
        (field (name "MANUFACTURERPARTNUMBER") "RMCF0603JT10K0")
      )
      (libsource (lib "eagle-import") (part "RESISTOR_0603"))
    )
    (comp (ref "R28")
      (value "10k")
      (footprint "eagle-import:_0603")
      (description "RES 10K OHM 5%% 1/10W 0603")
      (fields
        (field (name "MANUFACTURER") "Stackpole Electronics Inc")
        (field (name "MANUFACTURERPARTNUMBER") "RMCF0603JT10K0")
      )
      (libsource (lib "eagle-import") (part "RESISTOR_0603"))
    )
    (comp (ref "R29")
      (value "10k")
      (footprint "eagle-import:_0603")
      (description "RES 10K OHM 5%% 1/10W 0603")
      (fields
        (field (name "MANUFACTURER") "Stackpole Electronics Inc")
        (field (name "MANUFACTURERPARTNUMBER") "RMCF0603JT10K0")
      )
      (libsource (lib "eagle-import") (part "RESISTOR_0603"))
    )
    (comp (ref "R30")
      (value "10k")
      (footprint "eagle-import:_0603")
      (description "RES 10K OHM 5%% 1/10W 0603")
      (fields
        (field (name "MANUFACTURER") "Stackpole Electronics Inc")
        (field (name "MANUFACTURERPARTNUMBER") "RMCF0603JT10K0")
      )
      (libsource (lib "eagle-import") (part "RESISTOR_0603"))
    )
    (comp (ref "R31")
      (value "10k")
      (footprint "eagle-import:_0603")
      (description "RES 10K OHM 5%% 1/10W 0603")
      (fields
        (field (name "MANUFACTURER") "Stackpole Electronics Inc")
        (field (name "MANUFACTURERPARTNUMBER") "RMCF0603JT10K0")
      )
      (libsource (lib "eagle-import") (part "RESISTOR_0603"))
    )
    (comp (ref "R32")
      (value "10k")
      (footprint "eagle-import:_0603")
      (description "RES 10K OHM 5%% 1/10W 0603")
      (fields
        (field (name "MANUFACTURER") "Stackpole Electronics Inc")
        (field (name "MANUFACTURERPARTNUMBER") "RMCF0603JT10K0")
      )
      (libsource (lib "eagle-import") (part "RESISTOR_0603"))
    )
    (comp (ref "R33")
      (value "10k")
      (footprint "eagle-import:_0603")
      (description "RES 10K OHM 5%% 1/10W 0603")
      (fields
        (field (name "MANUFACTURER") "Stackpole Electronics Inc")
        (field (name "MANUFACTURERPARTNUMBER") "RMCF0603JT10K0")
      )
      (libsource (lib "eagle-import") (part "RESISTOR_0603"))
    )
    (comp (ref "R34")
      (value "3k 1%")
      (footprint "eagle-import:_0603")
      (description "RES 3K OHM 1%% 1/10W 0603")
      (fields
        (field (name "MANUFACTURER") "Stackpole Electronics Inc")
        (field (name "MANUFACTURERPARTNUMBER") "RMCF0603FT3K00")
      )
      (libsource (lib "eagle-import") (part "RESISTOR_0603"))
    )
    (comp (ref "R35")
      (value "3k 1%")
      (footprint "eagle-import:_0603")
      (description "RES 3K OHM 1%% 1/10W 0603")
      (fields
        (field (name "MANUFACTURER") "Stackpole Electronics Inc")
        (field (name "MANUFACTURERPARTNUMBER") "RMCF0603FT3K00")
      )
      (libsource (lib "eagle-import") (part "RESISTOR_0603"))
    )
    (comp (ref "R36")
      (value "10k")
      (footprint "eagle-import:_0603")
      (description "RES 10K OHM 5%% 1/10W 0603")
      (fields
        (field (name "MANUFACTURER") "Stackpole Electronics Inc")
        (field (name "MANUFACTURERPARTNUMBER") "RMCF0603JT10K0")
      )
      (libsource (lib "eagle-import") (part "RESISTOR_0603"))
    )
    (comp (ref "R37")
      (value "10k")
      (footprint "eagle-import:_0603")
      (description "RES 10K OHM 5%% 1/10W 0603")
      (fields
        (field (name "MANUFACTURER") "Stackpole Electronics Inc")
        (field (name "MANUFACTURERPARTNUMBER") "RMCF0603JT10K0")
      )
      (libsource (lib "eagle-import") (part "RESISTOR_0603"))
    )
    (comp (ref "R38")
      (value "120")
      (footprint "eagle-import:_0603")
      (description "RES 120 OHM 5%% 1/10W 0603")
      (fields
        (field (name "MANUFACTURER") "Stackpole Electronics Inc")
        (field (name "MANUFACTURERPARTNUMBER") "RMCF0603JT120R")
      )
      (libsource (lib "eagle-import") (part "RESISTOR_0603"))
    )
    (comp (ref "R39")
      (value "120")
      (footprint "eagle-import:_0603")
      (description "RES 120 OHM 5%% 1/10W 0603")
      (fields
        (field (name "MANUFACTURER") "Stackpole Electronics Inc")
        (field (name "MANUFACTURERPARTNUMBER") "RMCF0603JT120R")
      )
      (libsource (lib "eagle-import") (part "RESISTOR_0603"))
    )
    (comp (ref "R40")
      (value "330")
      (footprint "eagle-import:_0603")
      (description "RES SMD 330 OHM 1%% 1/10W 0603")
      (fields
        (field (name "MANUFACTURER") "Yageo")
        (field (name "MANUFACTURERPARTNUMBER") "RC0603FR-07330RL")
      )
      (libsource (lib "eagle-import") (part "RESISTOR_0603"))
    )
    (comp (ref "R41")
      (value "330")
      (footprint "eagle-import:_0603")
      (description "RES SMD 330 OHM 1%% 1/10W 0603")
      (fields
        (field (name "MANUFACTURER") "Yageo")
        (field (name "MANUFACTURERPARTNUMBER") "RC0603FR-07330RL")
      )
      (libsource (lib "eagle-import") (part "RESISTOR_0603"))
    )
    (comp (ref "R42")
      (value "1k")
      (footprint "eagle-import:_0603")
      (description "RES 1K OHM 5%% 1/10W 0603")
      (fields
        (field (name "MANUFACTURER") "Stackpole Electronics Inc")
        (field (name "MANUFACTURERPARTNUMBER") "RMCF0603JT1K00")
      )
      (libsource (lib "eagle-import") (part "RESISTOR_0603"))
    )
    (comp (ref "R43")
      (value "1k")
      (footprint "eagle-import:_0603")
      (description "RES 1K OHM 5%% 1/10W 0603")
      (fields
        (field (name "MANUFACTURER") "Stackpole Electronics Inc")
        (field (name "MANUFACTURERPARTNUMBER") "RMCF0603JT1K00")
      )
      (libsource (lib "eagle-import") (part "RESISTOR_0603"))
    )
    (comp (ref "R44")
      (value "DNP")
      (footprint "eagle-import:_0603")
      (description "RES SMD 0 OHM JUMPER 1/10W 0603")
      (fields
        (field (name "MANUFACTURER") "Panasonic Electronic Components")
        (field (name "MANUFACTURERPARTNUMBER") "ERJ-3GEY0R00V")
      )
      (libsource (lib "eagle-import") (part "RESISTOR_0603"))
    )
    (comp (ref "R45")
      (value "DNP")
      (footprint "eagle-import:_0603")
      (description "RES SMD 0 OHM JUMPER 1/10W 0603")
      (fields
        (field (name "MANUFACTURER") "Panasonic Electronic Components")
        (field (name "MANUFACTURERPARTNUMBER") "ERJ-3GEY0R00V")
      )
      (libsource (lib "eagle-import") (part "RESISTOR_0603"))
    )
    (comp (ref "R46")
      (value "DNP")
      (footprint "eagle-import:_0603")
      (description "RES SMD 0 OHM JUMPER 1/10W 0603")
      (fields
        (field (name "MANUFACTURER") "Panasonic Electronic Components")
        (field (name "MANUFACTURERPARTNUMBER") "ERJ-3GEY0R00V")
      )
      (libsource (lib "eagle-import") (part "RESISTOR_0603"))
    )
    (comp (ref "T1")
      (value "BC847C")
      (footprint "eagle-import:SOT23-BEC")
      (description "TRANS NPN 45V 0.1A SOT23")
      (fields
        (field (name "MANUFACTURER") "Nexperia USA Inc.")
        (field (name "MANUFACTURERPARTNUMBER") "BC847C,215")
      )
      (libsource (lib "eagle-import") (part "-NPN-SOT23-BECBC847C"))
    )
    (comp (ref "T2")
      (value "BC847C")
      (footprint "eagle-import:SOT23-BEC")
      (description "TRANS NPN 45V 0.1A SOT23")
      (fields
        (field (name "MANUFACTURER") "Nexperia USA Inc.")
        (field (name "MANUFACTURERPARTNUMBER") "BC847C,215")
      )
      (libsource (lib "eagle-import") (part "-NPN-SOT23-BECBC847C"))
    )
    (comp (ref "TP1")
      (value "TPTP12R")
      (footprint "eagle-import:TP12R")
      (description "NO DESCRIPTION")
      (fields
        (field (name "MANUFACTURER") "UNKNOWN MANUFACTURER")
        (field (name "MANUFACTURERPARTNUMBER") "UNKNOWN MANUFACTURER PART NUMBER")
      )
      (libsource (lib "eagle-import") (part "TPTP12R"))
    )
    (comp (ref "TP2")
      (value "TPTP12R")
      (footprint "eagle-import:TP12R")
      (description "NO DESCRIPTION")
      (fields
        (field (name "MANUFACTURER") "UNKNOWN MANUFACTURER")
        (field (name "MANUFACTURERPARTNUMBER") "UNKNOWN MANUFACTURER PART NUMBER")
      )
      (libsource (lib "eagle-import") (part "TPTP12R"))
    )
    (comp (ref "TP3")
      (value "TPTP12R")
      (footprint "eagle-import:TP12R")
      (description "NO DESCRIPTION")
      (fields
        (field (name "MANUFACTURER") "UNKNOWN MANUFACTURER")
        (field (name "MANUFACTURERPARTNUMBER") "UNKNOWN MANUFACTURER PART NUMBER")
      )
      (libsource (lib "eagle-import") (part "TPTP12R"))
    )
    (comp (ref "TP4")
      (value "TPTP12R")
      (footprint "eagle-import:TP12R")
      (description "NO DESCRIPTION")
      (fields
        (field (name "MANUFACTURER") "UNKNOWN MANUFACTURER")
        (field (name "MANUFACTURERPARTNUMBER") "UNKNOWN MANUFACTURER PART NUMBER")
      )
      (libsource (lib "eagle-import") (part "TPTP12R"))
    )
    (comp (ref "TR1")
      (value "PULSE_T1094NL")
      (footprint "eagle-import:PULSE_BH")
      (description "TRANSFORMER TELECOM DUAL T1/E2")
      (fields
        (field (name "MANUFACTURER") "Pulse Electronics Network")
        (field (name "MANUFACTURERPARTNUMBER") "T1094NL")
      )
      (libsource (lib "eagle-import") (part "PULSE_T1094NL"))
    )
    (comp (ref "TR2")
      (value "PULSE_T1094NL")
      (footprint "eagle-import:PULSE_BH")
      (description "TRANSFORMER TELECOM DUAL T1/E2")
      (fields
        (field (name "MANUFACTURER") "Pulse Electronics Network")
        (field (name "MANUFACTURERPARTNUMBER") "T1094NL")
      )
      (libsource (lib "eagle-import") (part "PULSE_T1094NL"))
    )
    (comp (ref "U4")
      (value "IDT82V2081")
      (footprint "eagle-import:TQFP44")
      (description "IC TELECOM INTERFACE 44TQFP")
      (fields
        (field (name "CLASS") "IC")
        (field (name "LINK") "https://www.digikey.de/product-detail/de/renesas-electronics-america-inc/82V2081PPG/800-2347-ND")
        (field (name "MANUFACTURER") "Renesas Electronics America Inc.")
        (field (name "MANUFACTURERPARTNUMBER") "82V2081PPG")
        (field (name "POPULATED") "TRUE")
        (field (name "ROHSCERTIFICATE") "UNKNOWN ROHS CERTIFICATE")
        (field (name "SOURCE") "DIGIKEY")
        (field (name "SOURCEPARTNUMBER") "800-2347-ND")
      )
      (libsource (lib "eagle-import") (part "IDT82V2081"))
    )
    (comp (ref "U5")
      (value "IDT82V2081")
      (footprint "eagle-import:TQFP44")
      (description "IC TELECOM INTERFACE 44TQFP")
      (fields
        (field (name "CLASS") "IC")
        (field (name "LINK") "https://www.digikey.de/product-detail/de/renesas-electronics-america-inc/82V2081PPG/800-2347-ND")
        (field (name "MANUFACTURER") "Renesas Electronics America Inc.")
        (field (name "MANUFACTURERPARTNUMBER") "82V2081PPG")
        (field (name "POPULATED") "TRUE")
        (field (name "ROHSCERTIFICATE") "UNKNOWN ROHS CERTIFICATE")
        (field (name "SOURCE") "DIGIKEY")
        (field (name "SOURCEPARTNUMBER") "800-2347-ND")
      )
      (libsource (lib "eagle-import") (part "IDT82V2081"))
    )
    (comp (ref "U6")
      (value "2.048 Mhz")
      (footprint "eagle-import:HC73")
      (description "XTAL OSC XO 2.0480MHZ HCMOS SMD")
      (fields
        (field (name "MANUFACTURER") "Renesas Electronics America Inc.")
        (field (name "MANUFACTURERPARTNUMBER") "XLH736002.048000I")
      )
      (libsource (lib "eagle-import") (part "FOX_FXO-HC73"))
    )
    (comp (ref "U7")
      (value "1.544 MHz")
      (footprint "eagle-import:HC73")
      (description "NO DESCRIPTION")
      (fields
        (field (name "MANUFACTURER") "UNKNOWN MANUFACTURER")
        (field (name "MANUFACTURERPARTNUMBER") "UNKNOWN MANUFACTURER PART NUMBER")
      )
      (libsource (lib "eagle-import") (part "FOX_FXO-HC73"))
    )
  )
  (nets
    (net (code "6") (name "BOOT_SW") (class "Default")
      (node (ref "SW1") (pin "2") (pinfunction "2_2") (pintype "passive"))
      (node (ref "U1") (pin "25") (pinfunction "IOT_36B_25") (pintype "bidirectional"))
    )
    (net (code "7") (name "CDONE") (class "Default")
      (node (ref "CDONE") (pin "A") (pinfunction "A_A") (pintype "passive"))
      (node (ref "JP1") (pin "6") (pinfunction "6_6") (pintype "passive"))
      (node (ref "R14") (pin "2") (pinfunction "2_2") (pintype "passive"))
      (node (ref "U1") (pin "7") (pinfunction "CDONE_7") (pintype "output"))
    )
    (net (code "8") (name "CLK_12M") (class "Default")
      (node (ref "IC4") (pin "3") (pinfunction "OUT_3") (pintype "output"))
      (node (ref "U1") (pin "20") (pinfunction "IOB_25B_G3_20") (pintype "bidirectional"))
    )
    (net (code "9") (name "GND") (class "Default")
      (node (ref "C1") (pin "1") (pinfunction "1_1") (pintype "passive"))
      (node (ref "C10") (pin "2") (pinfunction "2_2") (pintype "passive"))
      (node (ref "C11") (pin "2") (pinfunction "2_2") (pintype "passive"))
      (node (ref "C12") (pin "2") (pinfunction "2_2") (pintype "passive"))
      (node (ref "C13") (pin "2") (pinfunction "2_2") (pintype "passive"))
      (node (ref "C14") (pin "2") (pinfunction "2_2") (pintype "passive"))
      (node (ref "C15") (pin "2") (pinfunction "2_2") (pintype "passive"))
      (node (ref "C16") (pin "2") (pinfunction "2_2") (pintype "passive"))
      (node (ref "C17") (pin "2") (pinfunction "2_2") (pintype "passive"))
      (node (ref "C18") (pin "2") (pinfunction "2_2") (pintype "passive"))
      (node (ref "C19") (pin "2") (pinfunction "2_2") (pintype "passive"))
      (node (ref "C2") (pin "1") (pinfunction "1_1") (pintype "passive"))
      (node (ref "C20") (pin "2") (pinfunction "2_2") (pintype "passive"))
      (node (ref "C21") (pin "2") (pinfunction "2_2") (pintype "passive"))
      (node (ref "C22") (pin "2") (pinfunction "2_2") (pintype "passive"))
      (node (ref "C23") (pin "2") (pinfunction "2_2") (pintype "passive"))
      (node (ref "C24") (pin "2") (pinfunction "2_2") (pintype "passive"))
      (node (ref "C25") (pin "1") (pinfunction "1_1") (pintype "passive"))
      (node (ref "C26") (pin "1") (pinfunction "1_1") (pintype "passive"))
      (node (ref "C27") (pin "1") (pinfunction "1_1") (pintype "passive"))
      (node (ref "C28") (pin "1") (pinfunction "1_1") (pintype "passive"))
      (node (ref "C29") (pin "1") (pinfunction "1_1") (pintype "passive"))
      (node (ref "C3") (pin "1") (pinfunction "1_1") (pintype "passive"))
      (node (ref "C30") (pin "1") (pinfunction "1_1") (pintype "passive"))
      (node (ref "C4") (pin "1") (pinfunction "1_1") (pintype "passive"))
      (node (ref "C5") (pin "1") (pinfunction "1_1") (pintype "passive"))
      (node (ref "C6") (pin "1") (pinfunction "1_1") (pintype "passive"))
      (node (ref "C7") (pin "1") (pinfunction "1_1") (pintype "passive"))
      (node (ref "C8") (pin "1") (pinfunction "1_1") (pintype "passive"))
      (node (ref "C9") (pin "2") (pinfunction "2_2") (pintype "passive"))
      (node (ref "CDONE") (pin "C") (pinfunction "C_C") (pintype "passive"))
      (node (ref "D5") (pin "2") (pinfunction "A_2") (pintype "passive"))
      (node (ref "D6") (pin "2") (pinfunction "A_2") (pintype "passive"))
      (node (ref "D7") (pin "2") (pinfunction "A_2") (pintype "passive"))
      (node (ref "D8") (pin "2") (pinfunction "A_2") (pintype "passive"))
      (node (ref "IC1") (pin "1") (pinfunction "GND_1") (pintype "power_in"))
      (node (ref "IC2") (pin "4") (pinfunction "GND_4") (pintype "power_in"))
      (node (ref "IC3") (pin "2") (pinfunction "GND_2") (pintype "power_in"))
      (node (ref "IC3") (pin "4") (pinfunction "GND_4") (pintype "power_in"))
      (node (ref "IC4") (pin "2") (pinfunction "GND_2") (pintype "passive"))
      (node (ref "JP1") (pin "8") (pinfunction "8_8") (pintype "passive"))
      (node (ref "R11") (pin "1") (pinfunction "1_1") (pintype "passive"))
      (node (ref "R15") (pin "2") (pinfunction "2_2") (pintype "passive"))
      (node (ref "R16") (pin "2") (pinfunction "2_2") (pintype "passive"))
      (node (ref "R17") (pin "2") (pinfunction "2_2") (pintype "passive"))
      (node (ref "R18") (pin "2") (pinfunction "2_2") (pintype "passive"))
      (node (ref "R19") (pin "2") (pinfunction "2_2") (pintype "passive"))
      (node (ref "R20") (pin "2") (pinfunction "2_2") (pintype "passive"))
      (node (ref "R21") (pin "2") (pinfunction "2_2") (pintype "passive"))
      (node (ref "R22") (pin "2") (pinfunction "2_2") (pintype "passive"))
      (node (ref "R23") (pin "2") (pinfunction "2_2") (pintype "passive"))
      (node (ref "R25") (pin "2") (pinfunction "2_2") (pintype "passive"))
      (node (ref "R26") (pin "2") (pinfunction "2_2") (pintype "passive"))
      (node (ref "R27") (pin "2") (pinfunction "2_2") (pintype "passive"))
      (node (ref "R28") (pin "2") (pinfunction "2_2") (pintype "passive"))
      (node (ref "R29") (pin "2") (pinfunction "2_2") (pintype "passive"))
      (node (ref "R30") (pin "2") (pinfunction "2_2") (pintype "passive"))
      (node (ref "R31") (pin "2") (pinfunction "2_2") (pintype "passive"))
      (node (ref "R32") (pin "2") (pinfunction "2_2") (pintype "passive"))
      (node (ref "R34") (pin "1") (pinfunction "1_1") (pintype "passive"))
      (node (ref "R35") (pin "1") (pinfunction "1_1") (pintype "passive"))
      (node (ref "R45") (pin "2") (pinfunction "2_2") (pintype "passive"))
      (node (ref "R46") (pin "1") (pinfunction "1_1") (pintype "passive"))
      (node (ref "SW1") (pin "1") (pinfunction "1_1") (pintype "passive"))
      (node (ref "SW1") (pin "3") (pinfunction "3_3") (pintype "passive"))
      (node (ref "T1") (pin "E") (pinfunction "E_E") (pintype "passive"))
      (node (ref "T2") (pin "E") (pinfunction "E_E") (pintype "passive"))
      (node (ref "U1") (pin "EXP") (pinfunction "GND_EXP") (pintype "bidirectional"))
      (node (ref "U2") (pin "2") (pinfunction "GND_2") (pintype "passive"))
      (node (ref "U3") (pin "2") (pinfunction "GND_2") (pintype "passive"))
      (node (ref "U4") (pin "10") (pinfunction "GNDD_10") (pintype "power_in"))
      (node (ref "U4") (pin "11") (pinfunction "RCLKE_11") (pintype "input"))
      (node (ref "U4") (pin "13") (pinfunction "THZ_13") (pintype "input"))
      (node (ref "U4") (pin "14") (pinfunction "JA0_14") (pintype "input"))
      (node (ref "U4") (pin "15") (pinfunction "JA1_15") (pintype "input"))
      (node (ref "U4") (pin "17") (pinfunction "MODE1_17") (pintype "input"))
      (node (ref "U4") (pin "18") (pinfunction "GNDIO_18") (pintype "power_in"))
      (node (ref "U4") (pin "22") (pinfunction "~{RD/DS/SCLKE}_22") (pintype "input"))
      (node (ref "U4") (pin "38") (pinfunction "GNDT_38") (pintype "power_in"))
      (node (ref "U4") (pin "39") (pinfunction "GNDA_39") (pintype "power_in"))
      (node (ref "U5") (pin "10") (pinfunction "GNDD_10") (pintype "power_in"))
      (node (ref "U5") (pin "11") (pinfunction "RCLKE_11") (pintype "input"))
      (node (ref "U5") (pin "13") (pinfunction "THZ_13") (pintype "input"))
      (node (ref "U5") (pin "14") (pinfunction "JA0_14") (pintype "input"))
      (node (ref "U5") (pin "15") (pinfunction "JA1_15") (pintype "input"))
      (node (ref "U5") (pin "17") (pinfunction "MODE1_17") (pintype "input"))
      (node (ref "U5") (pin "18") (pinfunction "GNDIO_18") (pintype "power_in"))
      (node (ref "U5") (pin "22") (pinfunction "~{RD/DS/SCLKE}_22") (pintype "input"))
      (node (ref "U5") (pin "38") (pinfunction "GNDT_38") (pintype "power_in"))
      (node (ref "U5") (pin "39") (pinfunction "GNDA_39") (pintype "power_in"))
      (node (ref "U6") (pin "P$2") (pinfunction "GND_P$2") (pintype "power_in"))
      (node (ref "U7") (pin "P$2") (pinfunction "GND_P$2") (pintype "power_in"))
      (node (ref "X1") (pin "5") (pinfunction "5_5") (pintype "input"))
      (node (ref "X2") (pin "1") (pinfunction "RING_1") (pintype "passive"))
    )
    (net (code "10") (name "IOB_32A_SPI_SO") (class "Default")
      (node (ref "IC2") (pin "2") (pinfunction "SO(D1)_2") (pintype "bidirectional"))
      (node (ref "JP1") (pin "2") (pinfunction "2_2") (pintype "passive"))
      (node (ref "U1") (pin "14") (pinfunction "IOB_32A_SPI_SO_14") (pintype "bidirectional"))
    )
    (net (code "11") (name "IOB_33B_SPI_SI") (class "Default")
      (node (ref "IC2") (pin "5") (pinfunction "SI(D0)_5") (pintype "bidirectional"))
      (node (ref "JP1") (pin "3") (pinfunction "3_3") (pintype "passive"))
      (node (ref "U1") (pin "17") (pinfunction "IOB_33B_SPI_SI_17") (pintype "bidirectional"))
    )
    (net (code "12") (name "IOB_34A_SPI_SCK") (class "Default")
      (node (ref "IC2") (pin "6") (pinfunction "SCK_6") (pintype "input"))
      (node (ref "JP1") (pin "4") (pinfunction "4_4") (pintype "passive"))
      (node (ref "R10") (pin "1") (pinfunction "1_1") (pintype "passive"))
      (node (ref "U1") (pin "15") (pinfunction "IOB_34A_SPI_SCK_15") (pintype "bidirectional"))
    )
    (net (code "13") (name "IOB_35B_SPI_SS") (class "Default")
      (node (ref "IC2") (pin "1") (pinfunction "~{CS}_1") (pintype "input"))
      (node (ref "JP1") (pin "5") (pinfunction "5_5") (pintype "passive"))
      (node (ref "R8") (pin "1") (pinfunction "1_1") (pintype "passive"))
      (node (ref "U1") (pin "16") (pinfunction "IOB_35B_SPI_SS_16") (pintype "bidirectional"))
    )
    (net (code "14") (name "IO_A0") (class "Default")
      (node (ref "U1") (pin "31") (pinfunction "IOT_42B_31") (pintype "bidirectional"))
      (node (ref "U4") (pin "24") (pinfunction "SDI/WR/RW_24") (pintype "input"))
      (node (ref "U5") (pin "24") (pinfunction "SDI/WR/RW_24") (pintype "input"))
    )
    (net (code "15") (name "IO_A1") (class "Default")
      (node (ref "U1") (pin "32") (pinfunction "IOT_43A_32") (pintype "bidirectional"))
      (node (ref "U4") (pin "23") (pinfunction "SDO/~{ACK/RDY}_23") (pintype "output"))
      (node (ref "U5") (pin "23") (pinfunction "SDO/~{ACK/RDY}_23") (pintype "output"))
    )
    (net (code "16") (name "IO_A2") (class "Default")
      (node (ref "U1") (pin "34") (pinfunction "IOT_44B_34") (pintype "bidirectional"))
      (node (ref "U4") (pin "25") (pinfunction "SCLK/ALE/AS_25") (pintype "input"))
      (node (ref "U5") (pin "25") (pinfunction "SCLK/ALE/AS_25") (pintype "input"))
    )
    (net (code "17") (name "IO_A3") (class "Default")
      (node (ref "U1") (pin "38") (pinfunction "IOT_50B_38") (pintype "bidirectional"))
      (node (ref "U3") (pin "3") (pinfunction "1B_3") (pintype "passive"))
    )
    (net (code "18") (name "IO_A4") (class "Default")
      (node (ref "U1") (pin "42") (pinfunction "IOT_51A_42") (pintype "bidirectional"))
      (node (ref "U4") (pin "21") (pinfunction "~{CS}_21") (pintype "input"))
    )
    (net (code "19") (name "IO_A5") (class "Default")
      (node (ref "U1") (pin "43") (pinfunction "IOT_49A_43") (pintype "bidirectional"))
      (node (ref "U5") (pin "21") (pinfunction "~{CS}_21") (pintype "input"))
    )
    (net (code "20") (name "IO_B0") (class "Default")
      (node (ref "U1") (pin "44") (pinfunction "IOB_3B_G6_44") (pintype "bidirectional"))
      (node (ref "U4") (pin "4") (pinfunction "RCLK_4") (pintype "output"))
    )
    (net (code "21") (name "IO_B1") (class "Default")
      (node (ref "U1") (pin "45") (pinfunction "IOB_5B_45") (pintype "bidirectional"))
      (node (ref "U4") (pin "5") (pinfunction "RD/RDP_5") (pintype "output"))
    )
    (net (code "22") (name "IO_B2") (class "Default")
      (node (ref "U1") (pin "46") (pinfunction "IOB_0A_46") (pintype "bidirectional"))
      (node (ref "U5") (pin "4") (pinfunction "RCLK_4") (pintype "output"))
    )
    (net (code "23") (name "IO_B3") (class "Default")
      (node (ref "U1") (pin "47") (pinfunction "IOB_2A_47") (pintype "bidirectional"))
      (node (ref "U5") (pin "5") (pinfunction "RD/RDP_5") (pintype "output"))
    )
    (net (code "24") (name "LOS0") (class "Default")
      (node (ref "R36") (pin "2") (pinfunction "2_2") (pintype "passive"))
      (node (ref "U4") (pin "7") (pinfunction "LOS_7") (pintype "output"))
    )
    (net (code "25") (name "LOS1") (class "Default")
      (node (ref "R37") (pin "2") (pinfunction "2_2") (pintype "passive"))
      (node (ref "U5") (pin "7") (pinfunction "LOS_7") (pintype "output"))
    )
    (net (code "26") (name "MCLK") (class "Default")
      (node (ref "R44") (pin "2") (pinfunction "2_2") (pintype "passive"))
      (node (ref "U4") (pin "9") (pinfunction "MCLK_9") (pintype "power_in"))
      (node (ref "U5") (pin "9") (pinfunction "MCLK_9") (pintype "power_in"))
      (node (ref "U6") (pin "P$3") (pinfunction "OUT_P$3") (pintype "output"))
      (node (ref "U7") (pin "P$3") (pinfunction "OUT_P$3") (pintype "output"))
    )
    (net (code "27") (name "Net-(D1-A)") (class "Default")
      (node (ref "D1") (pin "2") (pinfunction "A_2") (pintype "passive"))
      (node (ref "D5") (pin "1") (pinfunction "C_1") (pintype "passive"))
      (node (ref "R38") (pin "2") (pinfunction "2_2") (pintype "passive"))
      (node (ref "TP1") (pin "TP") (pinfunction "TP_TP") (pintype "input"))
      (node (ref "TR1") (pin "1") (pinfunction "P$4_1") (pintype "bidirectional"))
      (node (ref "U4") (pin "41") (pinfunction "RTIP_41") (pintype "input"))
    )
    (net (code "28") (name "Net-(D2-A)") (class "Default")
      (node (ref "D2") (pin "2") (pinfunction "A_2") (pintype "passive"))
      (node (ref "D6") (pin "1") (pinfunction "C_1") (pintype "passive"))
      (node (ref "R38") (pin "1") (pinfunction "1_1") (pintype "passive"))
      (node (ref "TP2") (pin "TP") (pinfunction "TP_TP") (pintype "input"))
      (node (ref "TR1") (pin "3") (pinfunction "P$6_3") (pintype "bidirectional"))
      (node (ref "U4") (pin "40") (pinfunction "RRING_40") (pintype "input"))
    )
    (net (code "29") (name "Net-(D3-A)") (class "Default")
      (node (ref "D3") (pin "2") (pinfunction "A_2") (pintype "passive"))
      (node (ref "D7") (pin "1") (pinfunction "C_1") (pintype "passive"))
      (node (ref "R39") (pin "2") (pinfunction "2_2") (pintype "passive"))
      (node (ref "TP3") (pin "TP") (pinfunction "TP_TP") (pintype "input"))
      (node (ref "TR2") (pin "1") (pinfunction "P$4_1") (pintype "bidirectional"))
      (node (ref "U5") (pin "41") (pinfunction "RTIP_41") (pintype "input"))
    )
    (net (code "30") (name "Net-(D4-A)") (class "Default")
      (node (ref "D4") (pin "2") (pinfunction "A_2") (pintype "passive"))
      (node (ref "D8") (pin "1") (pinfunction "C_1") (pintype "passive"))
      (node (ref "R39") (pin "1") (pinfunction "1_1") (pintype "passive"))
      (node (ref "TP4") (pin "TP") (pinfunction "TP_TP") (pintype "input"))
      (node (ref "TR2") (pin "3") (pinfunction "P$6_3") (pintype "bidirectional"))
      (node (ref "U5") (pin "40") (pinfunction "RRING_40") (pintype "input"))
    )
    (net (code "31") (name "Net-(IC4-OE{slash}~{ST})") (class "Default")
      (node (ref "IC4") (pin "1") (pinfunction "OE/~{ST}_1") (pintype "input"))
      (node (ref "R13") (pin "1") (pinfunction "1_1") (pintype "passive"))
    )
    (net (code "32") (name "Net-(J1A-1)") (class "Default")
      (node (ref "J1") (pin "1-1") (pinfunction "1_1-1") (pintype "passive"))
      (node (ref "J1") (pin "2-1") (pinfunction "1_2-1") (pintype "passive"))
      (node (ref "TR1") (pin "14") (pinfunction "P$3_14") (pintype "bidirectional"))
    )
    (net (code "33") (name "Net-(J1A-2)") (class "Default")
      (node (ref "J1") (pin "1-2") (pinfunction "2_1-2") (pintype "passive"))
      (node (ref "J1") (pin "2-2") (pinfunction "2_2-2") (pintype "passive"))
      (node (ref "R42") (pin "1") (pinfunction "1_1") (pintype "passive"))
    )
    (net (code "34") (name "Net-(J1A-3)") (class "Default")
      (node (ref "J1") (pin "1-3") (pinfunction "3_1-3") (pintype "passive"))
      (node (ref "J1") (pin "2-3") (pinfunction "3_2-3") (pintype "passive"))
    )
    (net (code "35") (name "Net-(J1A-4)") (class "Default")
      (node (ref "J1") (pin "1-4") (pinfunction "4_1-4") (pintype "passive"))
      (node (ref "J1") (pin "2-4") (pinfunction "4_2-4") (pintype "passive"))
      (node (ref "TR2") (pin "14") (pinfunction "P$3_14") (pintype "bidirectional"))
    )
    (net (code "36") (name "Net-(J1A-5)") (class "Default")
      (node (ref "J1") (pin "1-5") (pinfunction "5_1-5") (pintype "passive"))
      (node (ref "J1") (pin "2-5") (pinfunction "5_2-5") (pintype "passive"))
      (node (ref "R43") (pin "1") (pinfunction "1_1") (pintype "passive"))
    )
    (net (code "37") (name "Net-(J1A-6)") (class "Default")
      (node (ref "J1") (pin "1-6") (pinfunction "6_1-6") (pintype "passive"))
      (node (ref "J1") (pin "2-6") (pinfunction "6_2-6") (pintype "passive"))
    )
    (net (code "38") (name "Net-(J1A-7)") (class "Default")
      (node (ref "J1") (pin "1-7") (pinfunction "7_1-7") (pintype "passive"))
      (node (ref "J1") (pin "2-7") (pinfunction "7_2-7") (pintype "passive"))
    )
    (net (code "39") (name "Net-(J1A-8)") (class "Default")
      (node (ref "J1") (pin "1-8") (pinfunction "8_1-8") (pintype "passive"))
      (node (ref "J1") (pin "2-8") (pinfunction "8_2-8") (pintype "passive"))
    )
    (net (code "40") (name "Net-(L1-Pad1)") (class "Default")
      (node (ref "L1") (pin "1") (pinfunction "1_1") (pintype "bidirectional"))
      (node (ref "R7") (pin "2") (pinfunction "2_2") (pintype "passive"))
    )
    (net (code "41") (name "Net-(L1-Pad4)") (class "Default")
      (node (ref "L1") (pin "4") (pinfunction "4_4") (pintype "bidirectional"))
      (node (ref "R6") (pin "2") (pinfunction "2_2") (pintype "passive"))
    )
    (net (code "42") (name "Net-(LED1-BLUE)") (class "Default")
      (node (ref "LED1") (pin "3") (pinfunction "BLUE_3") (pintype "bidirectional"))
      (node (ref "R2") (pin "1") (pinfunction "1_1") (pintype "passive"))
      (node (ref "R4") (pin "1") (pinfunction "1_1") (pintype "passive"))
    )
    (net (code "43") (name "Net-(LED1-GRN)") (class "Default")
      (node (ref "LED1") (pin "4") (pinfunction "GRN_4") (pintype "bidirectional"))
      (node (ref "U1") (pin "40") (pinfunction "RGB1_40") (pintype "bidirectional"))
    )
    (net (code "44") (name "Net-(LED1-RED)") (class "Default")
      (node (ref "LED1") (pin "1") (pinfunction "RED_1") (pintype "bidirectional"))
      (node (ref "R3") (pin "2") (pinfunction "2_2") (pintype "passive"))
      (node (ref "R5") (pin "2") (pinfunction "2_2") (pintype "passive"))
    )
    (net (code "45") (name "Net-(LOS1-C)") (class "Default")
      (node (ref "LOS1") (pin "K") (pinfunction "C_K") (pintype "passive"))
      (node (ref "R40") (pin "1") (pinfunction "1_1") (pintype "passive"))
    )
    (net (code "46") (name "Net-(LOS2-C)") (class "Default")
      (node (ref "LOS2") (pin "K") (pinfunction "C_K") (pintype "passive"))
      (node (ref "R41") (pin "1") (pinfunction "1_1") (pintype "passive"))
    )
    (net (code "47") (name "Net-(PWR-C)") (class "Default")
      (node (ref "PWR") (pin "K") (pinfunction "C_K") (pintype "passive"))
      (node (ref "R15") (pin "1") (pinfunction "1_1") (pintype "passive"))
    )
    (net (code "48") (name "Net-(R11-Pad2)") (class "Default")
      (node (ref "R11") (pin "2") (pinfunction "2_2") (pintype "passive"))
      (node (ref "R12") (pin "1") (pinfunction "1_1") (pintype "passive"))
    )
    (net (code "49") (name "Net-(R36-Pad1)") (class "Default")
      (node (ref "R36") (pin "1") (pinfunction "1_1") (pintype "passive"))
      (node (ref "T1") (pin "B") (pinfunction "B_B") (pintype "passive"))
    )
    (net (code "50") (name "Net-(R37-Pad1)") (class "Default")
      (node (ref "R37") (pin "1") (pinfunction "1_1") (pintype "passive"))
      (node (ref "T2") (pin "B") (pinfunction "B_B") (pintype "passive"))
    )
    (net (code "51") (name "Net-(R40-Pad2)") (class "Default")
      (node (ref "R40") (pin "2") (pinfunction "2_2") (pintype "passive"))
      (node (ref "T1") (pin "C") (pinfunction "C_C") (pintype "passive"))
    )
    (net (code "52") (name "Net-(R41-Pad2)") (class "Default")
      (node (ref "R41") (pin "2") (pinfunction "2_2") (pintype "passive"))
      (node (ref "T2") (pin "C") (pinfunction "C_C") (pintype "passive"))
    )
    (net (code "53") (name "Net-(TR1A-P$1)") (class "Default")
      (node (ref "R42") (pin "2") (pinfunction "2_2") (pintype "passive"))
      (node (ref "TR1") (pin "16") (pinfunction "P$1_16") (pintype "bidirectional"))
    )
    (net (code "54") (name "Net-(TR2A-P$1)") (class "Default")
      (node (ref "R43") (pin "2") (pinfunction "2_2") (pintype "passive"))
      (node (ref "TR2") (pin "16") (pinfunction "P$1_16") (pintype "bidirectional"))
    )
    (net (code "55") (name "Net-(U1-RGB0)") (class "Default")
      (node (ref "R4") (pin "2") (pinfunction "2_2") (pintype "passive"))
      (node (ref "R5") (pin "1") (pinfunction "1_1") (pintype "passive"))
      (node (ref "U1") (pin "39") (pinfunction "RGB0_39") (pintype "bidirectional"))
    )
    (net (code "56") (name "Net-(U1-RGB2)") (class "Default")
      (node (ref "R2") (pin "2") (pinfunction "2_2") (pintype "passive"))
      (node (ref "R3") (pin "1") (pinfunction "1_1") (pintype "passive"))
      (node (ref "U1") (pin "41") (pinfunction "RGB2_41") (pintype "bidirectional"))
    )
    (net (code "57") (name "Net-(U1-VCC_PLL)") (class "Default")
      (node (ref "C7") (pin "2") (pinfunction "2_2") (pintype "passive"))
      (node (ref "C8") (pin "2") (pinfunction "2_2") (pintype "passive"))
      (node (ref "R1") (pin "1") (pinfunction "1_1") (pintype "passive"))
      (node (ref "U1") (pin "29") (pinfunction "VCC_PLL_29") (pintype "power_in"))
    )
    (net (code "58") (name "Net-(U2-1A)") (class "Default")
      (node (ref "U2") (pin "1") (pinfunction "1A_1") (pintype "passive"))
      (node (ref "X1") (pin "3") (pinfunction "3_3") (pintype "input"))
    )
    (net (code "59") (name "Net-(U2-1B)") (class "Default")
      (node (ref "L1") (pin "2") (pinfunction "2_2") (pintype "bidirectional"))
      (node (ref "R9") (pin "2") (pinfunction "2_2") (pintype "passive"))
      (node (ref "U2") (pin "3") (pinfunction "1B_3") (pintype "passive"))
    )
    (net (code "60") (name "Net-(U2-2A)") (class "Default")
      (node (ref "U2") (pin "6") (pinfunction "2A_6") (pintype "passive"))
      (node (ref "X1") (pin "2") (pinfunction "2_2") (pintype "input"))
    )
    (net (code "61") (name "Net-(U2-2B)") (class "Default")
      (node (ref "L1") (pin "3") (pinfunction "3_3") (pintype "bidirectional"))
      (node (ref "U2") (pin "4") (pinfunction "2B_4") (pintype "passive"))
    )
    (net (code "62") (name "Net-(U3-1A)") (class "Default")
      (node (ref "U3") (pin "1") (pinfunction "1A_1") (pintype "passive"))
      (node (ref "X2") (pin "3") (pinfunction "MIDDLE_3") (pintype "passive"))
    )
    (net (code "63") (name "Net-(U4D-EQ{slash}AD3)") (class "Default")
      (node (ref "R20") (pin "1") (pinfunction "1_1") (pintype "passive"))
      (node (ref "U4") (pin "29") (pinfunction "EQ/AD3_29") (pintype "input"))
    )
    (net (code "64") (name "Net-(U4D-PATT0{slash}AD0)") (class "Default")
      (node (ref "R23") (pin "1") (pinfunction "1_1") (pintype "passive"))
      (node (ref "U4") (pin "26") (pinfunction "PATT0/AD0_26") (pintype "input"))
    )
    (net (code "65") (name "Net-(U4D-PATT1{slash}AD1)") (class "Default")
      (node (ref "R22") (pin "1") (pinfunction "1_1") (pintype "passive"))
      (node (ref "U4") (pin "27") (pinfunction "PATT1/AD1_27") (pintype "input"))
    )
    (net (code "66") (name "Net-(U4D-PULS0{slash}AD4)") (class "Default")
      (node (ref "R19") (pin "1") (pinfunction "1_1") (pintype "passive"))
      (node (ref "U4") (pin "30") (pinfunction "PULS0/AD4_30") (pintype "input"))
    )
    (net (code "67") (name "Net-(U4D-PULS1{slash}AD5)") (class "Default")
      (node (ref "R18") (pin "1") (pinfunction "1_1") (pintype "passive"))
      (node (ref "U4") (pin "31") (pinfunction "PULS1/AD5_31") (pintype "input"))
    )
    (net (code "68") (name "Net-(U4D-PULS2{slash}AD6)") (class "Default")
      (node (ref "R17") (pin "1") (pinfunction "1_1") (pintype "passive"))
      (node (ref "U4") (pin "32") (pinfunction "PULS2/AD6_32") (pintype "input"))
    )
    (net (code "69") (name "Net-(U4D-PULS3{slash}AD7)") (class "Default")
      (node (ref "R16") (pin "1") (pinfunction "1_1") (pintype "passive"))
      (node (ref "U4") (pin "33") (pinfunction "PULS3/AD7_33") (pintype "input"))
    )
    (net (code "70") (name "Net-(U4D-RPD{slash}AD2)") (class "Default")
      (node (ref "R21") (pin "1") (pinfunction "1_1") (pintype "passive"))
      (node (ref "U4") (pin "28") (pinfunction "RPD/AD2_28") (pintype "input"))
    )
    (net (code "71") (name "Net-(U4D-~{RST})") (class "Default")
      (node (ref "R24") (pin "1") (pinfunction "1_1") (pintype "passive"))
      (node (ref "U4") (pin "12") (pinfunction "~{RST}_12") (pintype "input"))
    )
    (net (code "72") (name "Net-(U4E-REF)") (class "Default")
      (node (ref "R34") (pin "2") (pinfunction "2_2") (pintype "passive"))
      (node (ref "U4") (pin "43") (pinfunction "REF_43") (pintype "input"))
    )
    (net (code "73") (name "Net-(U4E-VDDA)") (class "Default")
      (node (ref "C23") (pin "1") (pinfunction "1_1") (pintype "passive"))
      (node (ref "C25") (pin "2") (pinfunction "2_2") (pintype "passive"))
      (node (ref "L2") (pin "1") (pinfunction "1_1") (pintype "passive"))
      (node (ref "U4") (pin "42") (pinfunction "VDDA_42") (pintype "power_in"))
    )
    (net (code "74") (name "Net-(U5D-EQ{slash}AD3)") (class "Default")
      (node (ref "R29") (pin "1") (pinfunction "1_1") (pintype "passive"))
      (node (ref "U5") (pin "29") (pinfunction "EQ/AD3_29") (pintype "input"))
    )
    (net (code "75") (name "Net-(U5D-PATT0{slash}AD0)") (class "Default")
      (node (ref "R32") (pin "1") (pinfunction "1_1") (pintype "passive"))
      (node (ref "U5") (pin "26") (pinfunction "PATT0/AD0_26") (pintype "input"))
    )
    (net (code "76") (name "Net-(U5D-PATT1{slash}AD1)") (class "Default")
      (node (ref "R31") (pin "1") (pinfunction "1_1") (pintype "passive"))
      (node (ref "U5") (pin "27") (pinfunction "PATT1/AD1_27") (pintype "input"))
    )
    (net (code "77") (name "Net-(U5D-PULS0{slash}AD4)") (class "Default")
      (node (ref "R28") (pin "1") (pinfunction "1_1") (pintype "passive"))
      (node (ref "U5") (pin "30") (pinfunction "PULS0/AD4_30") (pintype "input"))
    )
    (net (code "78") (name "Net-(U5D-PULS1{slash}AD5)") (class "Default")
      (node (ref "R27") (pin "1") (pinfunction "1_1") (pintype "passive"))
      (node (ref "U5") (pin "31") (pinfunction "PULS1/AD5_31") (pintype "input"))
    )
    (net (code "79") (name "Net-(U5D-PULS2{slash}AD6)") (class "Default")
      (node (ref "R26") (pin "1") (pinfunction "1_1") (pintype "passive"))
      (node (ref "U5") (pin "32") (pinfunction "PULS2/AD6_32") (pintype "input"))
    )
    (net (code "80") (name "Net-(U5D-PULS3{slash}AD7)") (class "Default")
      (node (ref "R25") (pin "1") (pinfunction "1_1") (pintype "passive"))
      (node (ref "U5") (pin "33") (pinfunction "PULS3/AD7_33") (pintype "input"))
    )
    (net (code "81") (name "Net-(U5D-RPD{slash}AD2)") (class "Default")
      (node (ref "R30") (pin "1") (pinfunction "1_1") (pintype "passive"))
      (node (ref "U5") (pin "28") (pinfunction "RPD/AD2_28") (pintype "input"))
    )
    (net (code "82") (name "Net-(U5D-~{RST})") (class "Default")
      (node (ref "R33") (pin "1") (pinfunction "1_1") (pintype "passive"))
      (node (ref "U5") (pin "12") (pinfunction "~{RST}_12") (pintype "input"))
    )
    (net (code "83") (name "Net-(U5E-REF)") (class "Default")
      (node (ref "R35") (pin "2") (pinfunction "2_2") (pintype "passive"))
      (node (ref "U5") (pin "43") (pinfunction "REF_43") (pintype "input"))
    )
    (net (code "84") (name "Net-(U5E-VDDA)") (class "Default")
      (node (ref "C24") (pin "1") (pinfunction "1_1") (pintype "passive"))
      (node (ref "C26") (pin "2") (pinfunction "2_2") (pintype "passive"))
      (node (ref "L3") (pin "1") (pinfunction "1_1") (pintype "passive"))
      (node (ref "U5") (pin "42") (pinfunction "VDDA_42") (pintype "power_in"))
    )
    (net (code "85") (name "Net-(U6-E{slash}D)") (class "Default")
      (node (ref "R45") (pin "1") (pinfunction "1_1") (pintype "passive"))
      (node (ref "U6") (pin "P$1") (pinfunction "E/D_P$1") (pintype "input"))
    )
    (net (code "86") (name "Net-(U7-E{slash}D)") (class "Default")
      (node (ref "R46") (pin "2") (pinfunction "2_2") (pintype "passive"))
      (node (ref "U7") (pin "P$1") (pinfunction "E/D_P$1") (pintype "input"))
    )
    (net (code "87") (name "Net-(X1B-S1)") (class "Default")
      (node (ref "C14") (pin "1") (pinfunction "1_1") (pintype "passive"))
      (node (ref "R12") (pin "2") (pinfunction "2_2") (pintype "passive"))
      (node (ref "X1") (pin "M1") (pinfunction "S1_M1") (pintype "passive"))
      (node (ref "X1") (pin "M4") (pinfunction "S4_M4") (pintype "passive"))
    )
    (net (code "88") (name "Net-(X1B-S2)") (class "Default")
      (node (ref "X1") (pin "M2") (pinfunction "S2_M2") (pintype "passive"))
      (node (ref "X1") (pin "M3") (pinfunction "S3_M3") (pintype "passive"))
    )
    (net (code "89") (name "TCLK") (class "Default")
      (node (ref "R44") (pin "1") (pinfunction "1_1") (pintype "passive"))
      (node (ref "U4") (pin "1") (pinfunction "TCLK_1") (pintype "input"))
      (node (ref "U5") (pin "1") (pinfunction "TCLK_1") (pintype "input"))
    )
    (net (code "90") (name "USB_D_N") (class "Default")
      (node (ref "R6") (pin "1") (pinfunction "1_1") (pintype "passive"))
      (node (ref "U1") (pin "9") (pinfunction "IOB_16A_9") (pintype "bidirectional"))
    )
    (net (code "91") (name "USB_D_P") (class "Default")
      (node (ref "R7") (pin "1") (pinfunction "1_1") (pintype "passive"))
      (node (ref "U1") (pin "10") (pinfunction "IOB_18A_10") (pintype "bidirectional"))
    )
    (net (code "92") (name "USB_PU") (class "Default")
      (node (ref "R9") (pin "1") (pinfunction "1_1") (pintype "passive"))
      (node (ref "U1") (pin "6") (pinfunction "IOB_13B_6") (pintype "bidirectional"))
    )
    (net (code "93") (name "VBUS") (class "Default")
      (node (ref "C12") (pin "1") (pinfunction "1_1") (pintype "passive"))
      (node (ref "C13") (pin "1") (pinfunction "1_1") (pintype "passive"))
      (node (ref "C9") (pin "1") (pinfunction "1_1") (pintype "passive"))
      (node (ref "IC1") (pin "3") (pinfunction "VIN_3") (pintype "power_in"))
      (node (ref "IC3") (pin "1") (pinfunction "IN_1") (pintype "power_in"))
      (node (ref "U2") (pin "5") (pinfunction "VCC_5") (pintype "passive"))
      (node (ref "X1") (pin "1") (pinfunction "1_1") (pintype "input"))
    )
    (net (code "94") (name "VCC_1V2") (class "Default")
      (node (ref "C10") (pin "1") (pinfunction "1_1") (pintype "passive"))
      (node (ref "C5") (pin "2") (pinfunction "2_2") (pintype "passive"))
      (node (ref "C6") (pin "2") (pinfunction "2_2") (pintype "passive"))
      (node (ref "IC1") (pin "2") (pinfunction "VO_2") (pintype "power_in"))
      (node (ref "IC3") (pin "3") (pinfunction "EN_3") (pintype "input"))
      (node (ref "R1") (pin "2") (pinfunction "2_2") (pintype "passive"))
      (node (ref "U1") (pin "30") (pinfunction "VCC_30") (pintype "power_in"))
      (node (ref "U1") (pin "5") (pinfunction "VCC_5") (pintype "power_in"))
    )
    (net (code "95") (name "VCC_3V3") (class "Default")
      (node (ref "C1") (pin "2") (pinfunction "2_2") (pintype "passive"))
      (node (ref "C11") (pin "1") (pinfunction "1_1") (pintype "passive"))
      (node (ref "C15") (pin "1") (pinfunction "1_1") (pintype "passive"))
      (node (ref "C16") (pin "1") (pinfunction "1_1") (pintype "passive"))
      (node (ref "C17") (pin "1") (pinfunction "1_1") (pintype "passive"))
      (node (ref "C18") (pin "1") (pinfunction "1_1") (pintype "passive"))
      (node (ref "C19") (pin "1") (pinfunction "1_1") (pintype "passive"))
      (node (ref "C2") (pin "2") (pinfunction "2_2") (pintype "passive"))
      (node (ref "C20") (pin "1") (pinfunction "1_1") (pintype "passive"))
      (node (ref "C21") (pin "1") (pinfunction "1_1") (pintype "passive"))
      (node (ref "C22") (pin "1") (pinfunction "1_1") (pintype "passive"))
      (node (ref "C27") (pin "2") (pinfunction "2_2") (pintype "passive"))
      (node (ref "C28") (pin "2") (pinfunction "2_2") (pintype "passive"))
      (node (ref "C29") (pin "2") (pinfunction "2_2") (pintype "passive"))
      (node (ref "C3") (pin "2") (pinfunction "2_2") (pintype "passive"))
      (node (ref "C30") (pin "2") (pinfunction "2_2") (pintype "passive"))
      (node (ref "C4") (pin "2") (pinfunction "2_2") (pintype "passive"))
      (node (ref "D1") (pin "1") (pinfunction "C_1") (pintype "passive"))
      (node (ref "D2") (pin "1") (pinfunction "C_1") (pintype "passive"))
      (node (ref "D3") (pin "1") (pinfunction "C_1") (pintype "passive"))
      (node (ref "D4") (pin "1") (pinfunction "C_1") (pintype "passive"))
      (node (ref "IC2") (pin "3") (pinfunction "~{WP(D2})_3") (pintype "bidirectional"))
      (node (ref "IC2") (pin "7") (pinfunction "~{HOLD(D3})_7") (pintype "bidirectional"))
      (node (ref "IC2") (pin "8") (pinfunction "VCC_8") (pintype "power_in"))
      (node (ref "IC3") (pin "5") (pinfunction "OUT_5") (pintype "power_in"))
      (node (ref "IC4") (pin "4") (pinfunction "VCC_4") (pintype "passive"))
      (node (ref "JP1") (pin "1") (pinfunction "1_1") (pintype "passive"))
      (node (ref "L2") (pin "2") (pinfunction "2_2") (pintype "passive"))
      (node (ref "L3") (pin "2") (pinfunction "2_2") (pintype "passive"))
      (node (ref "LED1") (pin "2") (pinfunction "ANODE_2") (pintype "power_in"))
      (node (ref "LOS1") (pin "A") (pinfunction "A_A") (pintype "passive"))
      (node (ref "LOS2") (pin "A") (pinfunction "A_A") (pintype "passive"))
      (node (ref "PWR") (pin "A") (pinfunction "A_A") (pintype "passive"))
      (node (ref "R10") (pin "2") (pinfunction "2_2") (pintype "passive"))
      (node (ref "R13") (pin "2") (pinfunction "2_2") (pintype "passive"))
      (node (ref "R14") (pin "1") (pinfunction "1_1") (pintype "passive"))
      (node (ref "R24") (pin "2") (pinfunction "2_2") (pintype "passive"))
      (node (ref "R33") (pin "2") (pinfunction "2_2") (pintype "passive"))
      (node (ref "R8") (pin "2") (pinfunction "2_2") (pintype "passive"))
      (node (ref "U1") (pin "1") (pinfunction "VCC_IO_2_1") (pintype "power_in"))
      (node (ref "U1") (pin "22") (pinfunction "VCC_IO_1_22") (pintype "power_in"))
      (node (ref "U1") (pin "24") (pinfunction "VPP_2V5_24") (pintype "power_in"))
      (node (ref "U1") (pin "33") (pinfunction "VCC_IO_0_33") (pintype "power_in"))
      (node (ref "U3") (pin "5") (pinfunction "VCC_5") (pintype "passive"))
      (node (ref "U4") (pin "16") (pinfunction "MODE0_16") (pintype "input"))
      (node (ref "U4") (pin "19") (pinfunction "VDDIO_19") (pintype "power_in"))
      (node (ref "U4") (pin "35") (pinfunction "VDDT_35") (pintype "power_in"))
      (node (ref "U4") (pin "8") (pinfunction "VDDD_8") (pintype "power_in"))
      (node (ref "U5") (pin "16") (pinfunction "MODE0_16") (pintype "input"))
      (node (ref "U5") (pin "19") (pinfunction "VDDIO_19") (pintype "power_in"))
      (node (ref "U5") (pin "35") (pinfunction "VDDT_35") (pintype "power_in"))
      (node (ref "U5") (pin "8") (pinfunction "VDDD_8") (pintype "power_in"))
      (node (ref "U6") (pin "P$4") (pinfunction "VCC_P$4") (pintype "power_in"))
      (node (ref "U7") (pin "P$4") (pinfunction "VCC_P$4") (pintype "power_in"))
    )
    (net (code "96") (name "unconnected-(TR1A-P$2-Pad15)") (class "Default")
      (node (ref "TR1") (pin "15") (pinfunction "P$2_15") (pintype "bidirectional"))
    )
    (net (code "97") (name "unconnected-(TR1A-P$5-Pad2)") (class "Default")
      (node (ref "TR1") (pin "2") (pinfunction "P$5_2") (pintype "bidirectional"))
    )
    (net (code "98") (name "unconnected-(TR2A-P$2-Pad15)") (class "Default")
      (node (ref "TR2") (pin "15") (pinfunction "P$2_15") (pintype "bidirectional"))
    )
    (net (code "99") (name "unconnected-(TR2A-P$5-Pad2)") (class "Default")
      (node (ref "TR2") (pin "2") (pinfunction "P$5_2") (pintype "bidirectional"))
    )
    (net (code "100") (name "unconnected-(U1-IOB_4A-Pad48)") (class "Default")
      (node (ref "U1") (pin "48") (pinfunction "IOB_4A_48") (pintype "bidirectional"))
    )
    (net (code "101") (name "unconnected-(U1-IOB_6A-Pad2)") (class "Default")
      (node (ref "U1") (pin "2") (pinfunction "IOB_6A_2") (pintype "bidirectional"))
    )
    (net (code "102") (name "unconnected-(U1-IOB_8A-Pad4)") (class "Default")
      (node (ref "U1") (pin "4") (pinfunction "IOB_8A_4") (pintype "bidirectional"))
    )
    (net (code "103") (name "unconnected-(U1-IOB_9B-Pad3)") (class "Default")
      (node (ref "U1") (pin "3") (pinfunction "IOB_9B_3") (pintype "bidirectional"))
    )
    (net (code "104") (name "unconnected-(U1-IOB_20A-Pad11)") (class "Default")
      (node (ref "U1") (pin "11") (pinfunction "IOB_20A_11") (pintype "bidirectional"))
    )
    (net (code "105") (name "unconnected-(U1-IOB_22A-Pad12)") (class "Default")
      (node (ref "U1") (pin "12") (pinfunction "IOB_22A_12") (pintype "bidirectional"))
    )
    (net (code "106") (name "unconnected-(U1-IOB_23B-Pad21)") (class "Default")
      (node (ref "U1") (pin "21") (pinfunction "IOB_23B_21") (pintype "bidirectional"))
    )
    (net (code "107") (name "unconnected-(U1-IOB_24A-Pad13)") (class "Default")
      (node (ref "U1") (pin "13") (pinfunction "IOB_24A_13") (pintype "bidirectional"))
    )
    (net (code "108") (name "unconnected-(U1-IOB_29B-Pad19)") (class "Default")
      (node (ref "U1") (pin "19") (pinfunction "IOB_29B_19") (pintype "bidirectional"))
    )
    (net (code "109") (name "unconnected-(U1-IOB_31B-Pad18)") (class "Default")
      (node (ref "U1") (pin "18") (pinfunction "IOB_31B_18") (pintype "bidirectional"))
    )
    (net (code "110") (name "unconnected-(U1-IOT_37A-Pad23)") (class "Default")
      (node (ref "U1") (pin "23") (pinfunction "IOT_37A_23") (pintype "bidirectional"))
    )
    (net (code "111") (name "unconnected-(U1-IOT_38B-Pad27)") (class "Default")
      (node (ref "U1") (pin "27") (pinfunction "IOT_38B_27") (pintype "bidirectional"))
    )
    (net (code "112") (name "unconnected-(U1-IOT_39A-Pad26)") (class "Default")
      (node (ref "U1") (pin "26") (pinfunction "IOT_39A_26") (pintype "bidirectional"))
    )
    (net (code "113") (name "unconnected-(U1-IOT_41A-Pad28)") (class "Default")
      (node (ref "U1") (pin "28") (pinfunction "IOT_41A_28") (pintype "bidirectional"))
    )
    (net (code "114") (name "unconnected-(U1-IOT_45A_G1-Pad37)") (class "Default")
      (node (ref "U1") (pin "37") (pinfunction "IOT_45A_G1_37") (pintype "bidirectional"))
    )
    (net (code "115") (name "unconnected-(U1-IOT_46B_G0-Pad35)") (class "Default")
      (node (ref "U1") (pin "35") (pinfunction "IOT_46B_G0_35") (pintype "bidirectional"))
    )
    (net (code "116") (name "unconnected-(U1-IOT_48B-Pad36)") (class "Default")
      (node (ref "U1") (pin "36") (pinfunction "IOT_48B_36") (pintype "bidirectional"))
    )
    (net (code "117") (name "unconnected-(U3-2A-Pad6)") (class "Default")
      (node (ref "U3") (pin "6") (pinfunction "2A_6") (pintype "passive"))
    )
    (net (code "118") (name "unconnected-(U3-2B-Pad4)") (class "Default")
      (node (ref "U3") (pin "4") (pinfunction "2B_4") (pintype "passive"))
    )
    (net (code "119") (name "unconnected-(U4A-CV{slash}RDN-Pad6)") (class "Default")
      (node (ref "U4") (pin "6") (pinfunction "CV/RDN_6") (pintype "output"))
    )
    (net (code "120") (name "unconnected-(U4A-TDN-Pad3)") (class "Default")
      (node (ref "U4") (pin "3") (pinfunction "TDN_3") (pintype "input"))
    )
    (net (code "121") (name "unconnected-(U4A-TD{slash}TDP-Pad2)") (class "Default")
      (node (ref "U4") (pin "2") (pinfunction "TD/TDP_2") (pintype "input"))
    )
    (net (code "122") (name "unconnected-(U4B-TRING-Pad36)") (class "Default")
      (node (ref "U4") (pin "36") (pinfunction "TRING_36") (pintype "output"))
    )
    (net (code "123") (name "unconnected-(U4B-TTIP-Pad37)") (class "Default")
      (node (ref "U4") (pin "37") (pinfunction "TTIP_37") (pintype "output"))
    )
    (net (code "124") (name "unconnected-(U4C-~{INT}-Pad20)") (class "Default")
      (node (ref "U4") (pin "20") (pinfunction "~{INT}_20") (pintype "output"))
    )
    (net (code "125") (name "unconnected-(U4F-IC0-Pad44)") (class "Default")
      (node (ref "U4") (pin "44") (pinfunction "IC0_44") (pintype "no_connect"))
    )
    (net (code "126") (name "unconnected-(U4F-IC1-Pad34)") (class "Default")
      (node (ref "U4") (pin "34") (pinfunction "IC1_34") (pintype "no_connect"))
    )
    (net (code "127") (name "unconnected-(U5A-CV{slash}RDN-Pad6)") (class "Default")
      (node (ref "U5") (pin "6") (pinfunction "CV/RDN_6") (pintype "output"))
    )
    (net (code "128") (name "unconnected-(U5A-TDN-Pad3)") (class "Default")
      (node (ref "U5") (pin "3") (pinfunction "TDN_3") (pintype "input"))
    )
    (net (code "129") (name "unconnected-(U5A-TD{slash}TDP-Pad2)") (class "Default")
      (node (ref "U5") (pin "2") (pinfunction "TD/TDP_2") (pintype "input"))
    )
    (net (code "130") (name "unconnected-(U5B-TRING-Pad36)") (class "Default")
      (node (ref "U5") (pin "36") (pinfunction "TRING_36") (pintype "output"))
    )
    (net (code "131") (name "unconnected-(U5B-TTIP-Pad37)") (class "Default")
      (node (ref "U5") (pin "37") (pinfunction "TTIP_37") (pintype "output"))
    )
    (net (code "132") (name "unconnected-(U5C-~{INT}-Pad20)") (class "Default")
      (node (ref "U5") (pin "20") (pinfunction "~{INT}_20") (pintype "output"))
    )
    (net (code "133") (name "unconnected-(U5F-IC0-Pad44)") (class "Default")
      (node (ref "U5") (pin "44") (pinfunction "IC0_44") (pintype "no_connect"))
    )
    (net (code "134") (name "unconnected-(U5F-IC1-Pad34)") (class "Default")
      (node (ref "U5") (pin "34") (pinfunction "IC1_34") (pintype "no_connect"))
    )
    (net (code "135") (name "unconnected-(X1-Pad4)") (class "Default")
      (node (ref "X1") (pin "4") (pinfunction "4_4") (pintype "input"))
    )
    (net (code "136") (name "unconnected-(X2-TIP-Pad2)") (class "Default")
      (node (ref "X2") (pin "2") (pinfunction "TIP_2") (pintype "passive"))
    )
    (net (code "137") (name "~{CRESET}") (class "Default")
      (node (ref "JP1") (pin "7") (pinfunction "7_7") (pintype "passive"))
      (node (ref "U1") (pin "8") (pinfunction "~{CRESET_B}_8") (pintype "bidirectional"))
    )
  )
)
